# SzineszFeny_2mm_V12.net
KiCad netlist of a schematic drawn in EAGLE
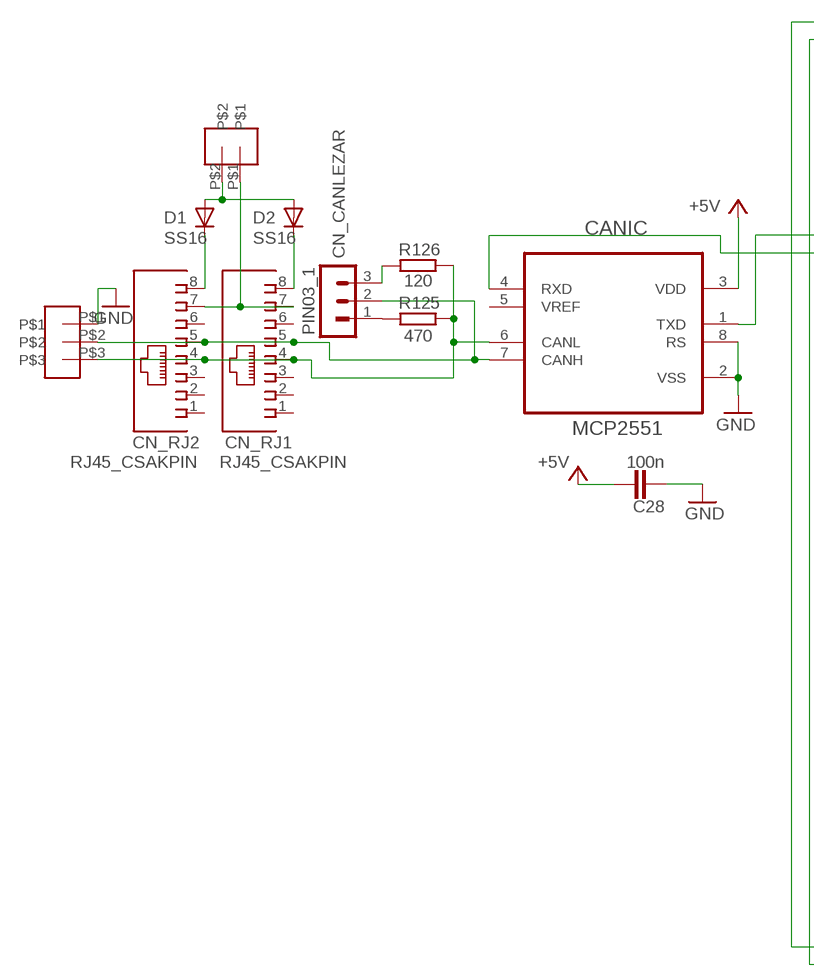
[diagram p0: schematic, sheet 1, part 1 of 2]
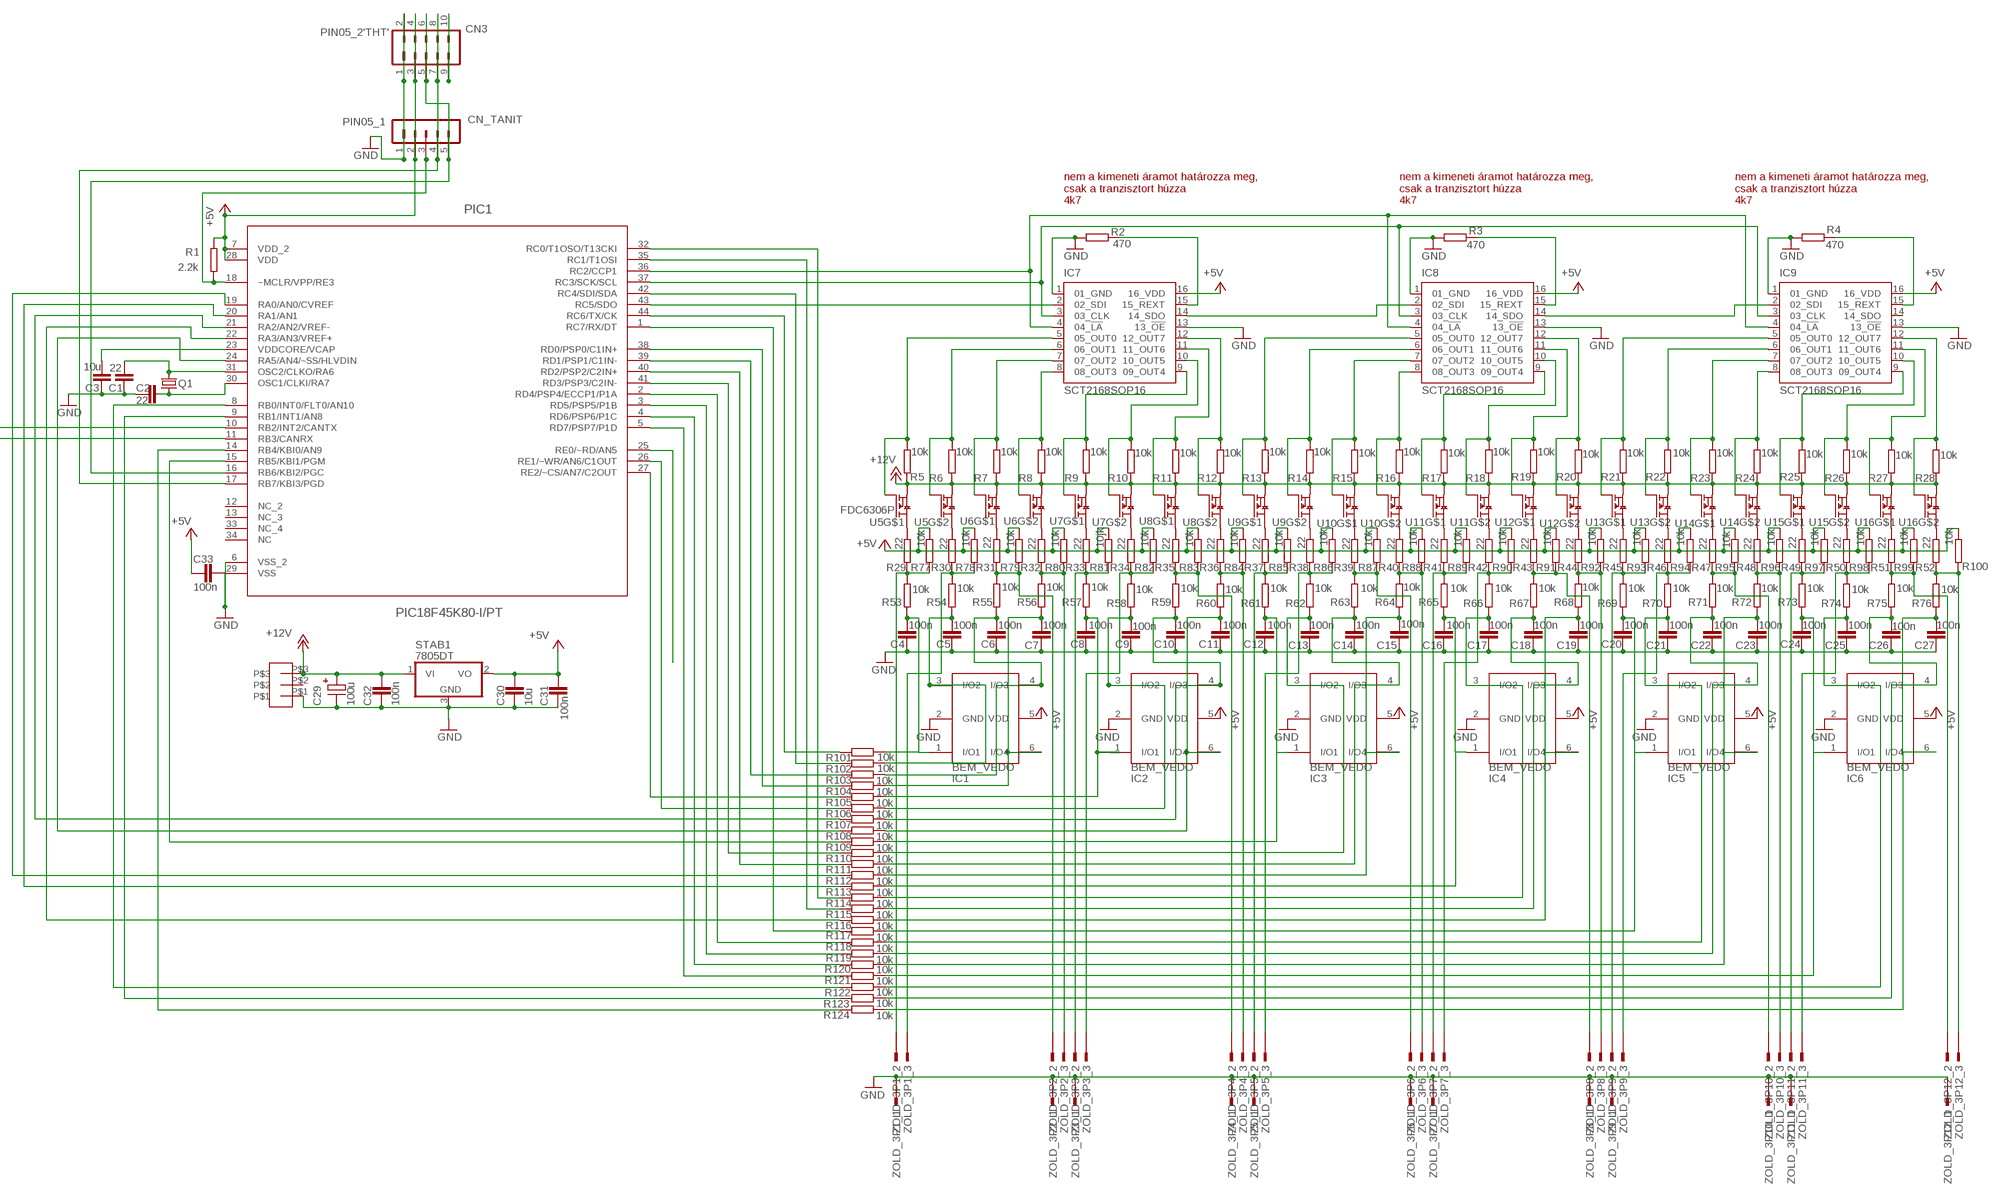
[diagram p1: schematic, sheet 1, part 2 of 2]

(export (version "E")
  (design (tool "Eeschema 10.0.6"))
  (components
    (comp (ref "C1")
      (value "22")
      (footprint "eagle-import:R0805")
      (libsource (lib "eagle-import") (part "C0805"))
    )
    (comp (ref "C2")
      (value "22")
      (footprint "eagle-import:R0805")
      (libsource (lib "eagle-import") (part "C0805"))
    )
    (comp (ref "C3")
      (value "10u")
      (footprint "eagle-import:R0805")
      (libsource (lib "eagle-import") (part "C0805"))
    )
    (comp (ref "C4")
      (value "100n")
      (footprint "eagle-import:R0805")
      (libsource (lib "eagle-import") (part "C0805"))
    )
    (comp (ref "C5")
      (value "100n")
      (footprint "eagle-import:R0805")
      (libsource (lib "eagle-import") (part "C0805"))
    )
    (comp (ref "C6")
      (value "100n")
      (footprint "eagle-import:R0805")
      (libsource (lib "eagle-import") (part "C0805"))
    )
    (comp (ref "C7")
      (value "100n")
      (footprint "eagle-import:R0805")
      (libsource (lib "eagle-import") (part "C0805"))
    )
    (comp (ref "C8")
      (value "100n")
      (footprint "eagle-import:R0805")
      (libsource (lib "eagle-import") (part "C0805"))
    )
    (comp (ref "C9")
      (value "100n")
      (footprint "eagle-import:R0805")
      (libsource (lib "eagle-import") (part "C0805"))
    )
    (comp (ref "C10")
      (value "100n")
      (footprint "eagle-import:R0805")
      (libsource (lib "eagle-import") (part "C0805"))
    )
    (comp (ref "C11")
      (value "100n")
      (footprint "eagle-import:R0805")
      (libsource (lib "eagle-import") (part "C0805"))
    )
    (comp (ref "C12")
      (value "100n")
      (footprint "eagle-import:R0805")
      (libsource (lib "eagle-import") (part "C0805"))
    )
    (comp (ref "C13")
      (value "100n")
      (footprint "eagle-import:R0805")
      (libsource (lib "eagle-import") (part "C0805"))
    )
    (comp (ref "C14")
      (value "100n")
      (footprint "eagle-import:R0805")
      (libsource (lib "eagle-import") (part "C0805"))
    )
    (comp (ref "C15")
      (value "100n")
      (footprint "eagle-import:R0805")
      (libsource (lib "eagle-import") (part "C0805"))
    )
    (comp (ref "C16")
      (value "100n")
      (footprint "eagle-import:R0805")
      (libsource (lib "eagle-import") (part "C0805"))
    )
    (comp (ref "C17")
      (value "100n")
      (footprint "eagle-import:R0805")
      (libsource (lib "eagle-import") (part "C0805"))
    )
    (comp (ref "C18")
      (value "100n")
      (footprint "eagle-import:R0805")
      (libsource (lib "eagle-import") (part "C0805"))
    )
    (comp (ref "C19")
      (value "100n")
      (footprint "eagle-import:R0805")
      (libsource (lib "eagle-import") (part "C0805"))
    )
    (comp (ref "C20")
      (value "100n")
      (footprint "eagle-import:R0805")
      (libsource (lib "eagle-import") (part "C0805"))
    )
    (comp (ref "C21")
      (value "100n")
      (footprint "eagle-import:R0805")
      (libsource (lib "eagle-import") (part "C0805"))
    )
    (comp (ref "C22")
      (value "100n")
      (footprint "eagle-import:R0805")
      (libsource (lib "eagle-import") (part "C0805"))
    )
    (comp (ref "C23")
      (value "100n")
      (footprint "eagle-import:R0805")
      (libsource (lib "eagle-import") (part "C0805"))
    )
    (comp (ref "C24")
      (value "100n")
      (footprint "eagle-import:R0805")
      (libsource (lib "eagle-import") (part "C0805"))
    )
    (comp (ref "C25")
      (value "100n")
      (footprint "eagle-import:R0805")
      (libsource (lib "eagle-import") (part "C0805"))
    )
    (comp (ref "C26")
      (value "100n")
      (footprint "eagle-import:R0805")
      (libsource (lib "eagle-import") (part "C0805"))
    )
    (comp (ref "C27")
      (value "100n")
      (footprint "eagle-import:R0805")
      (libsource (lib "eagle-import") (part "C0805"))
    )
    (comp (ref "C28")
      (value "100n")
      (footprint "eagle-import:R0805")
      (libsource (lib "eagle-import") (part "C0805"))
    )
    (comp (ref "C29")
      (value "100u")
      (footprint "eagle-import:C_EL1RASZT07")
      (libsource (lib "eagle-import") (part "C_EL1R07"))
    )
    (comp (ref "C30")
      (value "10u")
      (footprint "eagle-import:R0805")
      (libsource (lib "eagle-import") (part "C0805"))
    )
    (comp (ref "C31")
      (value "100n")
      (footprint "eagle-import:R0805")
      (libsource (lib "eagle-import") (part "C0805"))
    )
    (comp (ref "C32")
      (value "100n")
      (footprint "eagle-import:R0805")
      (libsource (lib "eagle-import") (part "C0805"))
    )
    (comp (ref "C33")
      (value "100n")
      (footprint "eagle-import:R0805")
      (libsource (lib "eagle-import") (part "C0805"))
    )
    (comp (ref "CANIC")
      (value "MCP2551")
      (footprint "eagle-import:DIP254P762X432-8")
      (fields (field (name "MPN") "MCP2551-I/P"))
      (libsource (lib "eagle-import") (part "MCP2551-I/P"))
    )
    (comp (ref "CN3")
      (value "PIN05_2'THT'")
      (footprint "eagle-import:PIN05_2")
      (libsource (lib "eagle-import") (part "PIN05_2'THT'"))
    )
    (comp (ref "CN_CANLEZAR")
      (value "PIN03_1")
      (footprint "eagle-import:PIN03_1")
      (libsource (lib "eagle-import") (part "PIN03_1"))
    )
    (comp (ref "CN_RJ1")
      (value "RJ45_CSAKPIN")
      (footprint "eagle-import:RJ45_CSAKPIN")
      (libsource (lib "eagle-import") (part "RJ45_CSAKPIN"))
    )
    (comp (ref "CN_RJ2")
      (value "RJ45_CSAKPIN")
      (footprint "eagle-import:RJ45_CSAKPIN")
      (libsource (lib "eagle-import") (part "RJ45_CSAKPIN"))
    )
    (comp (ref "CN_TANIT")
      (value "PIN05_1")
      (footprint "eagle-import:PIN05_1")
      (libsource (lib "eagle-import") (part "PIN05_1"))
    )
    (comp (ref "D1")
      (value "SS16")
      (footprint "eagle-import:DO214AC")
      (fields (field (name "D1") "SS16"))
      (libsource (lib "eagle-import") (part "DDO214AC"))
    )
    (comp (ref "D2")
      (value "SS16")
      (footprint "eagle-import:DO214AC")
      (fields (field (name "D2") "SS16"))
      (libsource (lib "eagle-import") (part "DDO214AC"))
    )
    (comp (ref "IC1")
      (value "BEM_VEDO")
      (footprint "eagle-import:TSOP-6")
      (libsource (lib "eagle-import") (part "BEM_VEDO"))
    )
    (comp (ref "IC2")
      (value "BEM_VEDO")
      (footprint "eagle-import:TSOP-6")
      (libsource (lib "eagle-import") (part "BEM_VEDO"))
    )
    (comp (ref "IC3")
      (value "BEM_VEDO")
      (footprint "eagle-import:TSOP-6")
      (libsource (lib "eagle-import") (part "BEM_VEDO"))
    )
    (comp (ref "IC4")
      (value "BEM_VEDO")
      (footprint "eagle-import:TSOP-6")
      (libsource (lib "eagle-import") (part "BEM_VEDO"))
    )
    (comp (ref "IC5")
      (value "BEM_VEDO")
      (footprint "eagle-import:TSOP-6")
      (libsource (lib "eagle-import") (part "BEM_VEDO"))
    )
    (comp (ref "IC6")
      (value "BEM_VEDO")
      (footprint "eagle-import:TSOP-6")
      (libsource (lib "eagle-import") (part "BEM_VEDO"))
    )
    (comp (ref "IC7")
      (value "SCT2168SOP16")
      (footprint "eagle-import:SO16")
      (libsource (lib "eagle-import") (part "SCT2168SOP16"))
    )
    (comp (ref "IC8")
      (value "SCT2168SOP16")
      (footprint "eagle-import:SO16")
      (libsource (lib "eagle-import") (part "SCT2168SOP16"))
    )
    (comp (ref "IC9")
      (value "SCT2168SOP16")
      (footprint "eagle-import:SO16")
      (libsource (lib "eagle-import") (part "SCT2168SOP16"))
    )
    (comp (ref "PIC1")
      (value "PIC18F45K80-I/PT")
      (footprint "eagle-import:QFP80P1200X1200X120-44N")
      (fields (field (name "MPN") "PIC18F4580-I/PT"))
      (libsource (lib "eagle-import") (part "PIC18F45K80-I/PT"))
    )
    (comp (ref "Q1")
      (value "XTAL_2QS")
      (footprint "eagle-import:XTAL_QS")
      (libsource (lib "eagle-import") (part "XTAL_2QS"))
    )
    (comp (ref "R1")
      (value "2.2k")
      (footprint "eagle-import:R0805@1")
      (libsource (lib "eagle-import") (part "R_EU0805"))
    )
    (comp (ref "R2")
      (value "470")
      (footprint "eagle-import:R0805@1")
      (libsource (lib "eagle-import") (part "R_EU0805"))
    )
    (comp (ref "R3")
      (value "470")
      (footprint "eagle-import:R0805@1")
      (libsource (lib "eagle-import") (part "R_EU0805"))
    )
    (comp (ref "R4")
      (value "470")
      (footprint "eagle-import:R0805@1")
      (libsource (lib "eagle-import") (part "R_EU0805"))
    )
    (comp (ref "R5")
      (value "10k")
      (footprint "eagle-import:R0805@1")
      (libsource (lib "eagle-import") (part "R_EU0805"))
    )
    (comp (ref "R6")
      (value "10k")
      (footprint "eagle-import:R0805@1")
      (libsource (lib "eagle-import") (part "R_EU0805"))
    )
    (comp (ref "R7")
      (value "10k")
      (footprint "eagle-import:R0805@1")
      (libsource (lib "eagle-import") (part "R_EU0805"))
    )
    (comp (ref "R8")
      (value "10k")
      (footprint "eagle-import:R0805@1")
      (libsource (lib "eagle-import") (part "R_EU0805"))
    )
    (comp (ref "R9")
      (value "10k")
      (footprint "eagle-import:R0805@1")
      (libsource (lib "eagle-import") (part "R_EU0805"))
    )
    (comp (ref "R10")
      (value "10k")
      (footprint "eagle-import:R0805@1")
      (libsource (lib "eagle-import") (part "R_EU0805"))
    )
    (comp (ref "R11")
      (value "10k")
      (footprint "eagle-import:R0805@1")
      (libsource (lib "eagle-import") (part "R_EU0805"))
    )
    (comp (ref "R12")
      (value "10k")
      (footprint "eagle-import:R0805@1")
      (libsource (lib "eagle-import") (part "R_EU0805"))
    )
    (comp (ref "R13")
      (value "10k")
      (footprint "eagle-import:R0805@1")
      (libsource (lib "eagle-import") (part "R_EU0805"))
    )
    (comp (ref "R14")
      (value "10k")
      (footprint "eagle-import:R0805@1")
      (libsource (lib "eagle-import") (part "R_EU0805"))
    )
    (comp (ref "R15")
      (value "10k")
      (footprint "eagle-import:R0805@1")
      (libsource (lib "eagle-import") (part "R_EU0805"))
    )
    (comp (ref "R16")
      (value "10k")
      (footprint "eagle-import:R0805@1")
      (libsource (lib "eagle-import") (part "R_EU0805"))
    )
    (comp (ref "R17")
      (value "10k")
      (footprint "eagle-import:R0805@1")
      (libsource (lib "eagle-import") (part "R_EU0805"))
    )
    (comp (ref "R18")
      (value "10k")
      (footprint "eagle-import:R0805@1")
      (libsource (lib "eagle-import") (part "R_EU0805"))
    )
    (comp (ref "R19")
      (value "10k")
      (footprint "eagle-import:R0805@1")
      (libsource (lib "eagle-import") (part "R_EU0805"))
    )
    (comp (ref "R20")
      (value "10k")
      (footprint "eagle-import:R0805@1")
      (libsource (lib "eagle-import") (part "R_EU0805"))
    )
    (comp (ref "R21")
      (value "10k")
      (footprint "eagle-import:R0805@1")
      (libsource (lib "eagle-import") (part "R_EU0805"))
    )
    (comp (ref "R22")
      (value "10k")
      (footprint "eagle-import:R0805@1")
      (libsource (lib "eagle-import") (part "R_EU0805"))
    )
    (comp (ref "R23")
      (value "10k")
      (footprint "eagle-import:R0805@1")
      (libsource (lib "eagle-import") (part "R_EU0805"))
    )
    (comp (ref "R24")
      (value "10k")
      (footprint "eagle-import:R0805@1")
      (libsource (lib "eagle-import") (part "R_EU0805"))
    )
    (comp (ref "R25")
      (value "10k")
      (footprint "eagle-import:R0805@1")
      (libsource (lib "eagle-import") (part "R_EU0805"))
    )
    (comp (ref "R26")
      (value "10k")
      (footprint "eagle-import:R0805@1")
      (libsource (lib "eagle-import") (part "R_EU0805"))
    )
    (comp (ref "R27")
      (value "10k")
      (footprint "eagle-import:R0805@1")
      (libsource (lib "eagle-import") (part "R_EU0805"))
    )
    (comp (ref "R28")
      (value "10k")
      (footprint "eagle-import:R0805@1")
      (libsource (lib "eagle-import") (part "R_EU0805"))
    )
    (comp (ref "R29")
      (value "22")
      (footprint "eagle-import:R0805@1")
      (libsource (lib "eagle-import") (part "R_EU0805"))
    )
    (comp (ref "R30")
      (value "22")
      (footprint "eagle-import:R0805@1")
      (libsource (lib "eagle-import") (part "R_EU0805"))
    )
    (comp (ref "R31")
      (value "22")
      (footprint "eagle-import:R0805@1")
      (libsource (lib "eagle-import") (part "R_EU0805"))
    )
    (comp (ref "R32")
      (value "22")
      (footprint "eagle-import:R0805@1")
      (libsource (lib "eagle-import") (part "R_EU0805"))
    )
    (comp (ref "R33")
      (value "22")
      (footprint "eagle-import:R0805@1")
      (libsource (lib "eagle-import") (part "R_EU0805"))
    )
    (comp (ref "R34")
      (value "22")
      (footprint "eagle-import:R0805@1")
      (libsource (lib "eagle-import") (part "R_EU0805"))
    )
    (comp (ref "R35")
      (value "22")
      (footprint "eagle-import:R0805@1")
      (libsource (lib "eagle-import") (part "R_EU0805"))
    )
    (comp (ref "R36")
      (value "22")
      (footprint "eagle-import:R0805@1")
      (libsource (lib "eagle-import") (part "R_EU0805"))
    )
    (comp (ref "R37")
      (value "22")
      (footprint "eagle-import:R0805@1")
      (libsource (lib "eagle-import") (part "R_EU0805"))
    )
    (comp (ref "R38")
      (value "22")
      (footprint "eagle-import:R0805@1")
      (libsource (lib "eagle-import") (part "R_EU0805"))
    )
    (comp (ref "R39")
      (value "22")
      (footprint "eagle-import:R0805@1")
      (libsource (lib "eagle-import") (part "R_EU0805"))
    )
    (comp (ref "R40")
      (value "22")
      (footprint "eagle-import:R0805@1")
      (libsource (lib "eagle-import") (part "R_EU0805"))
    )
    (comp (ref "R41")
      (value "22")
      (footprint "eagle-import:R0805@1")
      (libsource (lib "eagle-import") (part "R_EU0805"))
    )
    (comp (ref "R42")
      (value "22")
      (footprint "eagle-import:R0805@1")
      (libsource (lib "eagle-import") (part "R_EU0805"))
    )
    (comp (ref "R43")
      (value "22")
      (footprint "eagle-import:R0805@1")
      (libsource (lib "eagle-import") (part "R_EU0805"))
    )
    (comp (ref "R44")
      (value "22")
      (footprint "eagle-import:R0805@1")
      (libsource (lib "eagle-import") (part "R_EU0805"))
    )
    (comp (ref "R45")
      (value "22")
      (footprint "eagle-import:R0805@1")
      (libsource (lib "eagle-import") (part "R_EU0805"))
    )
    (comp (ref "R46")
      (value "22")
      (footprint "eagle-import:R0805@1")
      (libsource (lib "eagle-import") (part "R_EU0805"))
    )
    (comp (ref "R47")
      (value "22")
      (footprint "eagle-import:R0805@1")
      (libsource (lib "eagle-import") (part "R_EU0805"))
    )
    (comp (ref "R48")
      (value "22")
      (footprint "eagle-import:R0805@1")
      (libsource (lib "eagle-import") (part "R_EU0805"))
    )
    (comp (ref "R49")
      (value "22")
      (footprint "eagle-import:R0805@1")
      (libsource (lib "eagle-import") (part "R_EU0805"))
    )
    (comp (ref "R50")
      (value "22")
      (footprint "eagle-import:R0805@1")
      (libsource (lib "eagle-import") (part "R_EU0805"))
    )
    (comp (ref "R51")
      (value "22")
      (footprint "eagle-import:R0805@1")
      (libsource (lib "eagle-import") (part "R_EU0805"))
    )
    (comp (ref "R52")
      (value "22")
      (footprint "eagle-import:R0805@1")
      (libsource (lib "eagle-import") (part "R_EU0805"))
    )
    (comp (ref "R53")
      (value "10k")
      (footprint "eagle-import:R0805@1")
      (libsource (lib "eagle-import") (part "R_EU0805"))
    )
    (comp (ref "R54")
      (value "10k")
      (footprint "eagle-import:R0805@1")
      (libsource (lib "eagle-import") (part "R_EU0805"))
    )
    (comp (ref "R55")
      (value "10k")
      (footprint "eagle-import:R0805@1")
      (libsource (lib "eagle-import") (part "R_EU0805"))
    )
    (comp (ref "R56")
      (value "10k")
      (footprint "eagle-import:R0805@1")
      (libsource (lib "eagle-import") (part "R_EU0805"))
    )
    (comp (ref "R57")
      (value "10k")
      (footprint "eagle-import:R0805@1")
      (libsource (lib "eagle-import") (part "R_EU0805"))
    )
    (comp (ref "R58")
      (value "10k")
      (footprint "eagle-import:R0805@1")
      (libsource (lib "eagle-import") (part "R_EU0805"))
    )
    (comp (ref "R59")
      (value "10k")
      (footprint "eagle-import:R0805@1")
      (libsource (lib "eagle-import") (part "R_EU0805"))
    )
    (comp (ref "R60")
      (value "10k")
      (footprint "eagle-import:R0805@1")
      (libsource (lib "eagle-import") (part "R_EU0805"))
    )
    (comp (ref "R61")
      (value "10k")
      (footprint "eagle-import:R0805@1")
      (libsource (lib "eagle-import") (part "R_EU0805"))
    )
    (comp (ref "R62")
      (value "10k")
      (footprint "eagle-import:R0805@1")
      (libsource (lib "eagle-import") (part "R_EU0805"))
    )
    (comp (ref "R63")
      (value "10k")
      (footprint "eagle-import:R0805@1")
      (libsource (lib "eagle-import") (part "R_EU0805"))
    )
    (comp (ref "R64")
      (value "10k")
      (footprint "eagle-import:R0805@1")
      (libsource (lib "eagle-import") (part "R_EU0805"))
    )
    (comp (ref "R65")
      (value "10k")
      (footprint "eagle-import:R0805@1")
      (libsource (lib "eagle-import") (part "R_EU0805"))
    )
    (comp (ref "R66")
      (value "10k")
      (footprint "eagle-import:R0805@1")
      (libsource (lib "eagle-import") (part "R_EU0805"))
    )
    (comp (ref "R67")
      (value "10k")
      (footprint "eagle-import:R0805@1")
      (libsource (lib "eagle-import") (part "R_EU0805"))
    )
    (comp (ref "R68")
      (value "10k")
      (footprint "eagle-import:R0805@1")
      (libsource (lib "eagle-import") (part "R_EU0805"))
    )
    (comp (ref "R69")
      (value "10k")
      (footprint "eagle-import:R0805@1")
      (libsource (lib "eagle-import") (part "R_EU0805"))
    )
    (comp (ref "R70")
      (value "10k")
      (footprint "eagle-import:R0805@1")
      (libsource (lib "eagle-import") (part "R_EU0805"))
    )
    (comp (ref "R71")
      (value "10k")
      (footprint "eagle-import:R0805@1")
      (libsource (lib "eagle-import") (part "R_EU0805"))
    )
    (comp (ref "R72")
      (value "10k")
      (footprint "eagle-import:R0805@1")
      (libsource (lib "eagle-import") (part "R_EU0805"))
    )
    (comp (ref "R73")
      (value "10k")
      (footprint "eagle-import:R0805@1")
      (libsource (lib "eagle-import") (part "R_EU0805"))
    )
    (comp (ref "R74")
      (value "10k")
      (footprint "eagle-import:R0805@1")
      (libsource (lib "eagle-import") (part "R_EU0805"))
    )
    (comp (ref "R75")
      (value "10k")
      (footprint "eagle-import:R0805@1")
      (libsource (lib "eagle-import") (part "R_EU0805"))
    )
    (comp (ref "R76")
      (value "10k")
      (footprint "eagle-import:R0805@1")
      (libsource (lib "eagle-import") (part "R_EU0805"))
    )
    (comp (ref "R77")
      (value "10k")
      (footprint "eagle-import:R0805@1")
      (libsource (lib "eagle-import") (part "R_EU0805"))
    )
    (comp (ref "R78")
      (value "10k")
      (footprint "eagle-import:R0805@1")
      (libsource (lib "eagle-import") (part "R_EU0805"))
    )
    (comp (ref "R79")
      (value "10k")
      (footprint "eagle-import:R0805@1")
      (libsource (lib "eagle-import") (part "R_EU0805"))
    )
    (comp (ref "R80")
      (value "10k")
      (footprint "eagle-import:R0805@1")
      (libsource (lib "eagle-import") (part "R_EU0805"))
    )
    (comp (ref "R81")
      (value "10jk")
      (footprint "eagle-import:R0805@1")
      (libsource (lib "eagle-import") (part "R_EU0805"))
    )
    (comp (ref "R82")
      (value "10k")
      (footprint "eagle-import:R0805@1")
      (libsource (lib "eagle-import") (part "R_EU0805"))
    )
    (comp (ref "R83")
      (value "10k")
      (footprint "eagle-import:R0805@1")
      (libsource (lib "eagle-import") (part "R_EU0805"))
    )
    (comp (ref "R84")
      (value "10k")
      (footprint "eagle-import:R0805@1")
      (libsource (lib "eagle-import") (part "R_EU0805"))
    )
    (comp (ref "R85")
      (value "10k")
      (footprint "eagle-import:R0805@1")
      (libsource (lib "eagle-import") (part "R_EU0805"))
    )
    (comp (ref "R86")
      (value "10k")
      (footprint "eagle-import:R0805@1")
      (libsource (lib "eagle-import") (part "R_EU0805"))
    )
    (comp (ref "R87")
      (value "10k")
      (footprint "eagle-import:R0805@1")
      (libsource (lib "eagle-import") (part "R_EU0805"))
    )
    (comp (ref "R88")
      (value "10k")
      (footprint "eagle-import:R0805@1")
      (libsource (lib "eagle-import") (part "R_EU0805"))
    )
    (comp (ref "R89")
      (value "10k")
      (footprint "eagle-import:R0805@1")
      (libsource (lib "eagle-import") (part "R_EU0805"))
    )
    (comp (ref "R90")
      (value "10k")
      (footprint "eagle-import:R0805@1")
      (libsource (lib "eagle-import") (part "R_EU0805"))
    )
    (comp (ref "R91")
      (value "10k")
      (footprint "eagle-import:R0805@1")
      (libsource (lib "eagle-import") (part "R_EU0805"))
    )
    (comp (ref "R92")
      (value "10k")
      (footprint "eagle-import:R0805@1")
      (libsource (lib "eagle-import") (part "R_EU0805"))
    )
    (comp (ref "R93")
      (value "10k")
      (footprint "eagle-import:R0805@1")
      (libsource (lib "eagle-import") (part "R_EU0805"))
    )
    (comp (ref "R94")
      (value "10k")
      (footprint "eagle-import:R0805@1")
      (libsource (lib "eagle-import") (part "R_EU0805"))
    )
    (comp (ref "R95")
      (value "10k")
      (footprint "eagle-import:R0805@1")
      (libsource (lib "eagle-import") (part "R_EU0805"))
    )
    (comp (ref "R96")
      (value "10k")
      (footprint "eagle-import:R0805@1")
      (libsource (lib "eagle-import") (part "R_EU0805"))
    )
    (comp (ref "R97")
      (value "10k")
      (footprint "eagle-import:R0805@1")
      (libsource (lib "eagle-import") (part "R_EU0805"))
    )
    (comp (ref "R98")
      (value "10k")
      (footprint "eagle-import:R0805@1")
      (libsource (lib "eagle-import") (part "R_EU0805"))
    )
    (comp (ref "R99")
      (value "10k")
      (footprint "eagle-import:R0805@1")
      (libsource (lib "eagle-import") (part "R_EU0805"))
    )
    (comp (ref "R100")
      (value "10k")
      (footprint "eagle-import:R0805@1")
      (libsource (lib "eagle-import") (part "R_EU0805"))
    )
    (comp (ref "R101")
      (value "10k")
      (footprint "eagle-import:R0805@1")
      (libsource (lib "eagle-import") (part "R_EU0805"))
    )
    (comp (ref "R102")
      (value "10k")
      (footprint "eagle-import:R0805@1")
      (libsource (lib "eagle-import") (part "R_EU0805"))
    )
    (comp (ref "R103")
      (value "10k")
      (footprint "eagle-import:R0805@1")
      (libsource (lib "eagle-import") (part "R_EU0805"))
    )
    (comp (ref "R104")
      (value "10k")
      (footprint "eagle-import:R0805@1")
      (libsource (lib "eagle-import") (part "R_EU0805"))
    )
    (comp (ref "R105")
      (value "10k")
      (footprint "eagle-import:R0805@1")
      (libsource (lib "eagle-import") (part "R_EU0805"))
    )
    (comp (ref "R106")
      (value "10k")
      (footprint "eagle-import:R0805@1")
      (libsource (lib "eagle-import") (part "R_EU0805"))
    )
    (comp (ref "R107")
      (value "10k")
      (footprint "eagle-import:R0805@1")
      (libsource (lib "eagle-import") (part "R_EU0805"))
    )
    (comp (ref "R108")
      (value "10k")
      (footprint "eagle-import:R0805@1")
      (libsource (lib "eagle-import") (part "R_EU0805"))
    )
    (comp (ref "R109")
      (value "10k")
      (footprint "eagle-import:R0805@1")
      (libsource (lib "eagle-import") (part "R_EU0805"))
    )
    (comp (ref "R110")
      (value "10k")
      (footprint "eagle-import:R0805@1")
      (libsource (lib "eagle-import") (part "R_EU0805"))
    )
    (comp (ref "R111")
      (value "10k")
      (footprint "eagle-import:R0805@1")
      (libsource (lib "eagle-import") (part "R_EU0805"))
    )
    (comp (ref "R112")
      (value "10k")
      (footprint "eagle-import:R0805@1")
      (libsource (lib "eagle-import") (part "R_EU0805"))
    )
    (comp (ref "R113")
      (value "10k")
      (footprint "eagle-import:R0805@1")
      (libsource (lib "eagle-import") (part "R_EU0805"))
    )
    (comp (ref "R114")
      (value "10k")
      (footprint "eagle-import:R0805@1")
      (libsource (lib "eagle-import") (part "R_EU0805"))
    )
    (comp (ref "R115")
      (value "10k")
      (footprint "eagle-import:R0805@1")
      (libsource (lib "eagle-import") (part "R_EU0805"))
    )
    (comp (ref "R116")
      (value "10k")
      (footprint "eagle-import:R0805@1")
      (libsource (lib "eagle-import") (part "R_EU0805"))
    )
    (comp (ref "R117")
      (value "10k")
      (footprint "eagle-import:R0805@1")
      (libsource (lib "eagle-import") (part "R_EU0805"))
    )
    (comp (ref "R118")
      (value "10k")
      (footprint "eagle-import:R0805@1")
      (libsource (lib "eagle-import") (part "R_EU0805"))
    )
    (comp (ref "R119")
      (value "10k")
      (footprint "eagle-import:R0805@1")
      (libsource (lib "eagle-import") (part "R_EU0805"))
    )
    (comp (ref "R120")
      (value "10k")
      (footprint "eagle-import:R0805@1")
      (libsource (lib "eagle-import") (part "R_EU0805"))
    )
    (comp (ref "R121")
      (value "10k")
      (footprint "eagle-import:R0805@1")
      (libsource (lib "eagle-import") (part "R_EU0805"))
    )
    (comp (ref "R122")
      (value "10k")
      (footprint "eagle-import:R0805@1")
      (libsource (lib "eagle-import") (part "R_EU0805"))
    )
    (comp (ref "R123")
      (value "10k")
      (footprint "eagle-import:R0805@1")
      (libsource (lib "eagle-import") (part "R_EU0805"))
    )
    (comp (ref "R124")
      (value "10k")
      (footprint "eagle-import:R0805@1")
      (libsource (lib "eagle-import") (part "R_EU0805"))
    )
    (comp (ref "R125")
      (value "470")
      (footprint "eagle-import:R0805@1")
      (libsource (lib "eagle-import") (part "R_EU0805"))
    )
    (comp (ref "R126")
      (value "120")
      (footprint "eagle-import:R0805@1")
      (libsource (lib "eagle-import") (part "R_EU0805"))
    )
    (comp (ref "STAB1")
      (value "7805DT")
      (footprint "eagle-import:TO252")
      (libsource (lib "eagle-import") (part "78DT05"))
    )
    (comp (ref "U$1")
      (value "FEHER_TUS_3")
      (footprint "eagle-import:FEHER_TUS_3")
      (libsource (lib "eagle-import") (part "FEHER_TUS_3"))
    )
    (comp (ref "U$20")
      (value "FEHER_TUS_3")
      (footprint "eagle-import:FEHER_TUS_3")
      (libsource (lib "eagle-import") (part "FEHER_TUS_3"))
    )
    (comp (ref "U$21")
      (value "FEHER_TUS_2ALLO")
      (footprint "eagle-import:FEHER_TUS_2")
      (libsource (lib "eagle-import") (part "FEHER_TUS_2ALLO"))
    )
    (comp (ref "U5")
      (value "FDC6306P")
      (footprint "eagle-import:SOT26")
      (libsource (lib "eagle-import") (part "AP2625GY-HF-3SOT26"))
    )
    (comp (ref "U6")
      (value "AP2625GY-HF-3SOT26")
      (footprint "eagle-import:SOT26")
      (libsource (lib "eagle-import") (part "AP2625GY-HF-3SOT26"))
    )
    (comp (ref "U7")
      (value "AP2625GY-HF-3SOT26")
      (footprint "eagle-import:SOT26")
      (libsource (lib "eagle-import") (part "AP2625GY-HF-3SOT26"))
    )
    (comp (ref "U8")
      (value "AP2625GY-HF-3SOT26")
      (footprint "eagle-import:SOT26")
      (libsource (lib "eagle-import") (part "AP2625GY-HF-3SOT26"))
    )
    (comp (ref "U9")
      (value "AP2625GY-HF-3SOT26")
      (footprint "eagle-import:SOT26")
      (libsource (lib "eagle-import") (part "AP2625GY-HF-3SOT26"))
    )
    (comp (ref "U10")
      (value "AP2625GY-HF-3SOT26")
      (footprint "eagle-import:SOT26")
      (libsource (lib "eagle-import") (part "AP2625GY-HF-3SOT26"))
    )
    (comp (ref "U11")
      (value "AP2625GY-HF-3SOT26")
      (footprint "eagle-import:SOT26")
      (libsource (lib "eagle-import") (part "AP2625GY-HF-3SOT26"))
    )
    (comp (ref "U12")
      (value "AP2625GY-HF-3SOT26")
      (footprint "eagle-import:SOT26")
      (libsource (lib "eagle-import") (part "AP2625GY-HF-3SOT26"))
    )
    (comp (ref "U13")
      (value "AP2625GY-HF-3SOT26")
      (footprint "eagle-import:SOT26")
      (libsource (lib "eagle-import") (part "AP2625GY-HF-3SOT26"))
    )
    (comp (ref "U14")
      (value "AP2625GY-HF-3SOT26")
      (footprint "eagle-import:SOT26")
      (libsource (lib "eagle-import") (part "AP2625GY-HF-3SOT26"))
    )
    (comp (ref "U15")
      (value "AP2625GY-HF-3SOT26")
      (footprint "eagle-import:SOT26")
      (libsource (lib "eagle-import") (part "AP2625GY-HF-3SOT26"))
    )
    (comp (ref "U16")
      (value "FDC6306P")
      (footprint "eagle-import:SOT26")
      (libsource (lib "eagle-import") (part "AP2625GY-HF-3SOT26"))
    )
    (comp (ref "ZOLD_3P1")
      (value "ZOLD_KICSI_3P")
      (footprint "eagle-import:ZOLD_KICSI_3P")
      (libsource (lib "eagle-import") (part "ZOLD_KICSI_3P"))
    )
    (comp (ref "ZOLD_3P2")
      (value "ZOLD_KICSI_3P")
      (footprint "eagle-import:ZOLD_KICSI_3P")
      (libsource (lib "eagle-import") (part "ZOLD_KICSI_3P"))
    )
    (comp (ref "ZOLD_3P3")
      (value "ZOLD_KICSI_3P")
      (footprint "eagle-import:ZOLD_KICSI_3P")
      (libsource (lib "eagle-import") (part "ZOLD_KICSI_3P"))
    )
    (comp (ref "ZOLD_3P4")
      (value "ZOLD_KICSI_3P")
      (footprint "eagle-import:ZOLD_KICSI_3P")
      (libsource (lib "eagle-import") (part "ZOLD_KICSI_3P"))
    )
    (comp (ref "ZOLD_3P5")
      (value "ZOLD_KICSI_3P")
      (footprint "eagle-import:ZOLD_KICSI_3P")
      (libsource (lib "eagle-import") (part "ZOLD_KICSI_3P"))
    )
    (comp (ref "ZOLD_3P6")
      (value "ZOLD_KICSI_3P")
      (footprint "eagle-import:ZOLD_KICSI_3P")
      (libsource (lib "eagle-import") (part "ZOLD_KICSI_3P"))
    )
    (comp (ref "ZOLD_3P7")
      (value "ZOLD_KICSI_3P")
      (footprint "eagle-import:ZOLD_KICSI_3P")
      (libsource (lib "eagle-import") (part "ZOLD_KICSI_3P"))
    )
    (comp (ref "ZOLD_3P8")
      (value "ZOLD_KICSI_3P")
      (footprint "eagle-import:ZOLD_KICSI_3P")
      (libsource (lib "eagle-import") (part "ZOLD_KICSI_3P"))
    )
    (comp (ref "ZOLD_3P9")
      (value "ZOLD_KICSI_3P")
      (footprint "eagle-import:ZOLD_KICSI_3P")
      (libsource (lib "eagle-import") (part "ZOLD_KICSI_3P"))
    )
    (comp (ref "ZOLD_3P10")
      (value "ZOLD_KICSI_3P")
      (footprint "eagle-import:ZOLD_KICSI_3P")
      (libsource (lib "eagle-import") (part "ZOLD_KICSI_3P"))
    )
    (comp (ref "ZOLD_3P11")
      (value "ZOLD_KICSI_3P")
      (footprint "eagle-import:ZOLD_KICSI_3P")
      (libsource (lib "eagle-import") (part "ZOLD_KICSI_3P"))
    )
    (comp (ref "ZOLD_3P12")
      (value "ZOLD_KICSI_3P")
      (footprint "eagle-import:ZOLD_KICSI_3P")
      (libsource (lib "eagle-import") (part "ZOLD_KICSI_3P"))
    )
  )
  (nets
    (net (code "1") (name "+5V") (class "Default")
      (node (ref "C28") (pin "1") (pinfunction "1_1") (pintype "passive"))
      (node (ref "C30") (pin "1") (pinfunction "1_1") (pintype "passive"))
      (node (ref "C31") (pin "1") (pinfunction "1_1") (pintype "passive"))
      (node (ref "C33") (pin "2") (pinfunction "2_2") (pintype "passive"))
      (node (ref "CANIC") (pin "3") (pinfunction "VDD_3") (pintype "power_in"))
      (node (ref "CN3") (pin "3") (pinfunction "3_3") (pintype "passive"))
      (node (ref "CN3") (pin "4") (pinfunction "4_4") (pintype "passive"))
      (node (ref "CN_TANIT") (pin "2") (pinfunction "2_2") (pintype "passive"))
      (node (ref "IC1") (pin "5") (pinfunction "VDD_5") (pintype "bidirectional"))
      (node (ref "IC2") (pin "5") (pinfunction "VDD_5") (pintype "bidirectional"))
      (node (ref "IC3") (pin "5") (pinfunction "VDD_5") (pintype "bidirectional"))
      (node (ref "IC4") (pin "5") (pinfunction "VDD_5") (pintype "bidirectional"))
      (node (ref "IC5") (pin "5") (pinfunction "VDD_5") (pintype "bidirectional"))
      (node (ref "IC6") (pin "5") (pinfunction "VDD_5") (pintype "bidirectional"))
      (node (ref "IC7") (pin "16") (pinfunction "16_VDD_16") (pintype "power_in"))
      (node (ref "IC8") (pin "16") (pinfunction "16_VDD_16") (pintype "power_in"))
      (node (ref "IC9") (pin "16") (pinfunction "16_VDD_16") (pintype "power_in"))
      (node (ref "PIC1") (pin "28") (pinfunction "VDD_28") (pintype "power_in"))
      (node (ref "PIC1") (pin "7") (pinfunction "VDD_2_7") (pintype "power_in"))
      (node (ref "R1") (pin "2") (pinfunction "E_2") (pintype "passive"))
      (node (ref "R100") (pin "1") (pinfunction "A_1") (pintype "passive"))
      (node (ref "R77") (pin "1") (pinfunction "A_1") (pintype "passive"))
      (node (ref "R78") (pin "1") (pinfunction "A_1") (pintype "passive"))
      (node (ref "R79") (pin "1") (pinfunction "A_1") (pintype "passive"))
      (node (ref "R80") (pin "1") (pinfunction "A_1") (pintype "passive"))
      (node (ref "R81") (pin "1") (pinfunction "A_1") (pintype "passive"))
      (node (ref "R82") (pin "1") (pinfunction "A_1") (pintype "passive"))
      (node (ref "R83") (pin "1") (pinfunction "A_1") (pintype "passive"))
      (node (ref "R84") (pin "1") (pinfunction "A_1") (pintype "passive"))
      (node (ref "R85") (pin "1") (pinfunction "A_1") (pintype "passive"))
      (node (ref "R86") (pin "1") (pinfunction "A_1") (pintype "passive"))
      (node (ref "R87") (pin "1") (pinfunction "A_1") (pintype "passive"))
      (node (ref "R88") (pin "1") (pinfunction "A_1") (pintype "passive"))
      (node (ref "R89") (pin "1") (pinfunction "A_1") (pintype "passive"))
      (node (ref "R90") (pin "1") (pinfunction "A_1") (pintype "passive"))
      (node (ref "R91") (pin "1") (pinfunction "A_1") (pintype "passive"))
      (node (ref "R92") (pin "1") (pinfunction "A_1") (pintype "passive"))
      (node (ref "R93") (pin "1") (pinfunction "A_1") (pintype "passive"))
      (node (ref "R94") (pin "1") (pinfunction "A_1") (pintype "passive"))
      (node (ref "R95") (pin "1") (pinfunction "A_1") (pintype "passive"))
      (node (ref "R96") (pin "1") (pinfunction "A_1") (pintype "passive"))
      (node (ref "R97") (pin "1") (pinfunction "A_1") (pintype "passive"))
      (node (ref "R98") (pin "1") (pinfunction "A_1") (pintype "passive"))
      (node (ref "R99") (pin "1") (pinfunction "A_1") (pintype "passive"))
      (node (ref "STAB1") (pin "2") (pinfunction "VO_2") (pintype "passive"))
    )
    (net (code "2") (name "+12V") (class "Default")
      (node (ref "C29") (pin "P+") (pinfunction "P+_P+") (pintype "passive"))
      (node (ref "C32") (pin "1") (pinfunction "1_1") (pintype "passive"))
      (node (ref "R10") (pin "1") (pinfunction "A_1") (pintype "passive"))
      (node (ref "R11") (pin "1") (pinfunction "A_1") (pintype "passive"))
      (node (ref "R12") (pin "1") (pinfunction "A_1") (pintype "passive"))
      (node (ref "R13") (pin "1") (pinfunction "A_1") (pintype "passive"))
      (node (ref "R14") (pin "1") (pinfunction "A_1") (pintype "passive"))
      (node (ref "R15") (pin "1") (pinfunction "A_1") (pintype "passive"))
      (node (ref "R16") (pin "1") (pinfunction "A_1") (pintype "passive"))
      (node (ref "R17") (pin "1") (pinfunction "A_1") (pintype "passive"))
      (node (ref "R18") (pin "1") (pinfunction "A_1") (pintype "passive"))
      (node (ref "R19") (pin "1") (pinfunction "A_1") (pintype "passive"))
      (node (ref "R20") (pin "1") (pinfunction "A_1") (pintype "passive"))
      (node (ref "R21") (pin "1") (pinfunction "A_1") (pintype "passive"))
      (node (ref "R22") (pin "1") (pinfunction "A_1") (pintype "passive"))
      (node (ref "R23") (pin "1") (pinfunction "A_1") (pintype "passive"))
      (node (ref "R24") (pin "1") (pinfunction "A_1") (pintype "passive"))
      (node (ref "R25") (pin "1") (pinfunction "A_1") (pintype "passive"))
      (node (ref "R26") (pin "1") (pinfunction "A_1") (pintype "passive"))
      (node (ref "R27") (pin "1") (pinfunction "A_1") (pintype "passive"))
      (node (ref "R28") (pin "1") (pinfunction "A_1") (pintype "passive"))
      (node (ref "R5") (pin "1") (pinfunction "A_1") (pintype "passive"))
      (node (ref "R6") (pin "1") (pinfunction "A_1") (pintype "passive"))
      (node (ref "R7") (pin "1") (pinfunction "A_1") (pintype "passive"))
      (node (ref "R8") (pin "1") (pinfunction "A_1") (pintype "passive"))
      (node (ref "R9") (pin "1") (pinfunction "A_1") (pintype "passive"))
      (node (ref "STAB1") (pin "1") (pinfunction "VI_1") (pintype "input"))
      (node (ref "U$20") (pin "P$3") (pinfunction "P$3_P$3") (pintype "bidirectional"))
      (node (ref "U10") (pin "P$2") (pinfunction "S_P$2") (pintype "passive"))
      (node (ref "U10") (pin "P$5") (pinfunction "S_P$5") (pintype "passive"))
      (node (ref "U11") (pin "P$2") (pinfunction "S_P$2") (pintype "passive"))
      (node (ref "U11") (pin "P$5") (pinfunction "S_P$5") (pintype "passive"))
      (node (ref "U12") (pin "P$2") (pinfunction "S_P$2") (pintype "passive"))
      (node (ref "U12") (pin "P$5") (pinfunction "S_P$5") (pintype "passive"))
      (node (ref "U13") (pin "P$2") (pinfunction "S_P$2") (pintype "passive"))
      (node (ref "U13") (pin "P$5") (pinfunction "S_P$5") (pintype "passive"))
      (node (ref "U14") (pin "P$2") (pinfunction "S_P$2") (pintype "passive"))
      (node (ref "U14") (pin "P$5") (pinfunction "S_P$5") (pintype "passive"))
      (node (ref "U15") (pin "P$2") (pinfunction "S_P$2") (pintype "passive"))
      (node (ref "U15") (pin "P$5") (pinfunction "S_P$5") (pintype "passive"))
      (node (ref "U16") (pin "P$2") (pinfunction "S_P$2") (pintype "passive"))
      (node (ref "U16") (pin "P$5") (pinfunction "S_P$5") (pintype "passive"))
      (node (ref "U5") (pin "P$2") (pinfunction "S_P$2") (pintype "passive"))
      (node (ref "U5") (pin "P$5") (pinfunction "S_P$5") (pintype "passive"))
      (node (ref "U6") (pin "P$2") (pinfunction "S_P$2") (pintype "passive"))
      (node (ref "U6") (pin "P$5") (pinfunction "S_P$5") (pintype "passive"))
      (node (ref "U7") (pin "P$2") (pinfunction "S_P$2") (pintype "passive"))
      (node (ref "U7") (pin "P$5") (pinfunction "S_P$5") (pintype "passive"))
      (node (ref "U8") (pin "P$2") (pinfunction "S_P$2") (pintype "passive"))
      (node (ref "U8") (pin "P$5") (pinfunction "S_P$5") (pintype "passive"))
      (node (ref "U9") (pin "P$2") (pinfunction "S_P$2") (pintype "passive"))
      (node (ref "U9") (pin "P$5") (pinfunction "S_P$5") (pintype "passive"))
    )
    (net (code "3") (name "GND") (class "Default")
      (node (ref "C1") (pin "2") (pinfunction "2_2") (pintype "passive"))
      (node (ref "C10") (pin "2") (pinfunction "2_2") (pintype "passive"))
      (node (ref "C11") (pin "2") (pinfunction "2_2") (pintype "passive"))
      (node (ref "C12") (pin "2") (pinfunction "2_2") (pintype "passive"))
      (node (ref "C13") (pin "2") (pinfunction "2_2") (pintype "passive"))
      (node (ref "C14") (pin "2") (pinfunction "2_2") (pintype "passive"))
      (node (ref "C15") (pin "2") (pinfunction "2_2") (pintype "passive"))
      (node (ref "C16") (pin "2") (pinfunction "2_2") (pintype "passive"))
      (node (ref "C17") (pin "2") (pinfunction "2_2") (pintype "passive"))
      (node (ref "C18") (pin "2") (pinfunction "2_2") (pintype "passive"))
      (node (ref "C19") (pin "2") (pinfunction "2_2") (pintype "passive"))
      (node (ref "C2") (pin "2") (pinfunction "2_2") (pintype "passive"))
      (node (ref "C20") (pin "2") (pinfunction "2_2") (pintype "passive"))
      (node (ref "C21") (pin "2") (pinfunction "2_2") (pintype "passive"))
      (node (ref "C22") (pin "2") (pinfunction "2_2") (pintype "passive"))
      (node (ref "C23") (pin "2") (pinfunction "2_2") (pintype "passive"))
      (node (ref "C24") (pin "2") (pinfunction "2_2") (pintype "passive"))
      (node (ref "C25") (pin "2") (pinfunction "2_2") (pintype "passive"))
      (node (ref "C26") (pin "2") (pinfunction "2_2") (pintype "passive"))
      (node (ref "C27") (pin "2") (pinfunction "2_2") (pintype "passive"))
      (node (ref "C28") (pin "2") (pinfunction "2_2") (pintype "passive"))
      (node (ref "C29") (pin "P-") (pinfunction "P-_P-") (pintype "passive"))
      (node (ref "C3") (pin "2") (pinfunction "2_2") (pintype "passive"))
      (node (ref "C30") (pin "2") (pinfunction "2_2") (pintype "passive"))
      (node (ref "C31") (pin "2") (pinfunction "2_2") (pintype "passive"))
      (node (ref "C32") (pin "2") (pinfunction "2_2") (pintype "passive"))
      (node (ref "C33") (pin "1") (pinfunction "1_1") (pintype "passive"))
      (node (ref "C4") (pin "2") (pinfunction "2_2") (pintype "passive"))
      (node (ref "C5") (pin "2") (pinfunction "2_2") (pintype "passive"))
      (node (ref "C6") (pin "2") (pinfunction "2_2") (pintype "passive"))
      (node (ref "C7") (pin "2") (pinfunction "2_2") (pintype "passive"))
      (node (ref "C8") (pin "2") (pinfunction "2_2") (pintype "passive"))
      (node (ref "C9") (pin "2") (pinfunction "2_2") (pintype "passive"))
      (node (ref "CANIC") (pin "2") (pinfunction "VSS_2") (pintype "power_in"))
      (node (ref "CANIC") (pin "8") (pinfunction "RS_8") (pintype "input"))
      (node (ref "CN3") (pin "1") (pinfunction "1_1") (pintype "passive"))
      (node (ref "CN3") (pin "2") (pinfunction "2_2") (pintype "passive"))
      (node (ref "CN_TANIT") (pin "1") (pinfunction "1_1") (pintype "passive"))
      (node (ref "IC1") (pin "2") (pinfunction "GND_2") (pintype "bidirectional"))
      (node (ref "IC2") (pin "2") (pinfunction "GND_2") (pintype "bidirectional"))
      (node (ref "IC3") (pin "2") (pinfunction "GND_2") (pintype "bidirectional"))
      (node (ref "IC4") (pin "2") (pinfunction "GND_2") (pintype "bidirectional"))
      (node (ref "IC5") (pin "2") (pinfunction "GND_2") (pintype "bidirectional"))
      (node (ref "IC6") (pin "2") (pinfunction "GND_2") (pintype "bidirectional"))
      (node (ref "IC7") (pin "1") (pinfunction "01_GND_1") (pintype "power_in"))
      (node (ref "IC7") (pin "13") (pinfunction "13_~{OE}_13") (pintype "input"))
      (node (ref "IC8") (pin "1") (pinfunction "01_GND_1") (pintype "power_in"))
      (node (ref "IC8") (pin "13") (pinfunction "13_~{OE}_13") (pintype "input"))
      (node (ref "IC9") (pin "1") (pinfunction "01_GND_1") (pintype "power_in"))
      (node (ref "IC9") (pin "13") (pinfunction "13_~{OE}_13") (pintype "input"))
      (node (ref "PIC1") (pin "29") (pinfunction "VSS_29") (pintype "power_in"))
      (node (ref "PIC1") (pin "6") (pinfunction "VSS_2_6") (pintype "power_in"))
      (node (ref "R2") (pin "1") (pinfunction "A_1") (pintype "passive"))
      (node (ref "R3") (pin "1") (pinfunction "A_1") (pintype "passive"))
      (node (ref "R4") (pin "1") (pinfunction "A_1") (pintype "passive"))
      (node (ref "STAB1") (pin "3") (pinfunction "GND_3") (pintype "passive"))
      (node (ref "U$1") (pin "P$1") (pinfunction "P$1_P$1") (pintype "bidirectional"))
      (node (ref "U$20") (pin "P$1") (pinfunction "P$1_P$1") (pintype "bidirectional"))
      (node (ref "ZOLD_3P1") (pin "1") (pinfunction "1_1") (pintype "passive"))
      (node (ref "ZOLD_3P10") (pin "1") (pinfunction "1_1") (pintype "passive"))
      (node (ref "ZOLD_3P11") (pin "1") (pinfunction "1_1") (pintype "passive"))
      (node (ref "ZOLD_3P12") (pin "1") (pinfunction "1_1") (pintype "passive"))
      (node (ref "ZOLD_3P2") (pin "1") (pinfunction "1_1") (pintype "passive"))
      (node (ref "ZOLD_3P3") (pin "1") (pinfunction "1_1") (pintype "passive"))
      (node (ref "ZOLD_3P4") (pin "1") (pinfunction "1_1") (pintype "passive"))
      (node (ref "ZOLD_3P5") (pin "1") (pinfunction "1_1") (pintype "passive"))
      (node (ref "ZOLD_3P6") (pin "1") (pinfunction "1_1") (pintype "passive"))
      (node (ref "ZOLD_3P7") (pin "1") (pinfunction "1_1") (pintype "passive"))
      (node (ref "ZOLD_3P8") (pin "1") (pinfunction "1_1") (pintype "passive"))
      (node (ref "ZOLD_3P9") (pin "1") (pinfunction "1_1") (pintype "passive"))
    )
    (net (code "4") (name "Net-(CANIC-CANH)") (class "Default")
      (node (ref "CANIC") (pin "7") (pinfunction "CANH_7") (pintype "bidirectional"))
      (node (ref "CN_CANLEZAR") (pin "2") (pinfunction "2_2") (pintype "passive"))
      (node (ref "CN_RJ1") (pin "5") (pinfunction "5_5") (pintype "passive"))
      (node (ref "CN_RJ2") (pin "5") (pinfunction "5_5") (pintype "passive"))
      (node (ref "U$1") (pin "P$2") (pinfunction "P$2_P$2") (pintype "bidirectional"))
    )
    (net (code "5") (name "Net-(CANIC-CANL)") (class "Default")
      (node (ref "CANIC") (pin "6") (pinfunction "CANL_6") (pintype "bidirectional"))
      (node (ref "CN_RJ1") (pin "4") (pinfunction "4_4") (pintype "passive"))
      (node (ref "CN_RJ2") (pin "4") (pinfunction "4_4") (pintype "passive"))
      (node (ref "R125") (pin "1") (pinfunction "A_1") (pintype "passive"))
      (node (ref "R126") (pin "2") (pinfunction "E_2") (pintype "passive"))
      (node (ref "U$1") (pin "P$3") (pinfunction "P$3_P$3") (pintype "bidirectional"))
    )
    (net (code "6") (name "Net-(CANIC-RXD)") (class "Default")
      (node (ref "CANIC") (pin "4") (pinfunction "RXD_4") (pintype "output"))
      (node (ref "PIC1") (pin "11") (pinfunction "RB3/CANRX_11") (pintype "bidirectional"))
    )
    (net (code "7") (name "Net-(CANIC-TXD)") (class "Default")
      (node (ref "CANIC") (pin "1") (pinfunction "TXD_1") (pintype "input"))
      (node (ref "PIC1") (pin "10") (pinfunction "RB2/INT2/CANTX_10") (pintype "bidirectional"))
    )
    (net (code "8") (name "Net-(CN3-Pad10)") (class "Default")
      (node (ref "CN3") (pin "10") (pinfunction "10_10") (pintype "passive"))
      (node (ref "CN3") (pin "9") (pinfunction "9_9") (pintype "passive"))
    )
    (net (code "9") (name "Net-(CN_RJ1-Pad7)") (class "Default")
      (node (ref "CN_RJ1") (pin "7") (pinfunction "7_7") (pintype "passive"))
      (node (ref "CN_RJ2") (pin "7") (pinfunction "7_7") (pintype "passive"))
      (node (ref "U$21") (pin "P$1") (pinfunction "P$1_P$1") (pintype "bidirectional"))
    )
    (net (code "10") (name "Net-(CN_RJ1-Pad8)") (class "Default")
      (node (ref "CN_RJ1") (pin "8") (pinfunction "8_8") (pintype "passive"))
      (node (ref "D2") (pin "C") (pinfunction "C_C") (pintype "passive"))
    )
    (net (code "11") (name "Net-(CN_RJ2-Pad8)") (class "Default")
      (node (ref "CN_RJ2") (pin "8") (pinfunction "8_8") (pintype "passive"))
      (node (ref "D1") (pin "C") (pinfunction "C_C") (pintype "passive"))
    )
    (net (code "12") (name "Net-(D1-PadA)") (class "Default")
      (node (ref "D1") (pin "A") (pinfunction "A_A") (pintype "passive"))
      (node (ref "D2") (pin "A") (pinfunction "A_A") (pintype "passive"))
      (node (ref "U$21") (pin "P$2") (pinfunction "P$2_P$2") (pintype "bidirectional"))
    )
    (net (code "13") (name "Net-(IC1-I{slash}O1)") (class "Default")
      (node (ref "C4") (pin "1") (pinfunction "1_1") (pintype "passive"))
      (node (ref "IC1") (pin "1") (pinfunction "I/O1_1") (pintype "bidirectional"))
      (node (ref "R101") (pin "2") (pinfunction "E_2") (pintype "passive"))
      (node (ref "R53") (pin "1") (pinfunction "A_1") (pintype "passive"))
    )
    (net (code "14") (name "Net-(IC1-I{slash}O2)") (class "Default")
      (node (ref "C5") (pin "1") (pinfunction "1_1") (pintype "passive"))
      (node (ref "IC1") (pin "3") (pinfunction "I/O2_3") (pintype "bidirectional"))
      (node (ref "R102") (pin "2") (pinfunction "E_2") (pintype "passive"))
      (node (ref "R54") (pin "1") (pinfunction "A_1") (pintype "passive"))
    )
    (net (code "15") (name "Net-(IC1-I{slash}O3)") (class "Default")
      (node (ref "C6") (pin "1") (pinfunction "1_1") (pintype "passive"))
      (node (ref "IC1") (pin "4") (pinfunction "I/O3_4") (pintype "bidirectional"))
      (node (ref "R103") (pin "2") (pinfunction "E_2") (pintype "passive"))
      (node (ref "R55") (pin "1") (pinfunction "A_1") (pintype "passive"))
    )
    (net (code "16") (name "Net-(IC1-I{slash}O4)") (class "Default")
      (node (ref "C7") (pin "1") (pinfunction "1_1") (pintype "passive"))
      (node (ref "IC1") (pin "6") (pinfunction "I/O4_6") (pintype "bidirectional"))
      (node (ref "R104") (pin "2") (pinfunction "E_2") (pintype "passive"))
      (node (ref "R56") (pin "1") (pinfunction "A_1") (pintype "passive"))
    )
    (net (code "17") (name "Net-(IC2-I{slash}O1)") (class "Default")
      (node (ref "C8") (pin "1") (pinfunction "1_1") (pintype "passive"))
      (node (ref "IC2") (pin "1") (pinfunction "I/O1_1") (pintype "bidirectional"))
      (node (ref "R105") (pin "2") (pinfunction "E_2") (pintype "passive"))
      (node (ref "R57") (pin "1") (pinfunction "A_1") (pintype "passive"))
    )
    (net (code "18") (name "Net-(IC2-I{slash}O2)") (class "Default")
      (node (ref "C9") (pin "1") (pinfunction "1_1") (pintype "passive"))
      (node (ref "IC2") (pin "3") (pinfunction "I/O2_3") (pintype "bidirectional"))
      (node (ref "R106") (pin "2") (pinfunction "E_2") (pintype "passive"))
      (node (ref "R58") (pin "1") (pinfunction "A_1") (pintype "passive"))
    )
    (net (code "19") (name "Net-(IC2-I{slash}O3)") (class "Default")
      (node (ref "C10") (pin "1") (pinfunction "1_1") (pintype "passive"))
      (node (ref "IC2") (pin "4") (pinfunction "I/O3_4") (pintype "bidirectional"))
      (node (ref "R107") (pin "2") (pinfunction "E_2") (pintype "passive"))
      (node (ref "R59") (pin "1") (pinfunction "A_1") (pintype "passive"))
    )
    (net (code "20") (name "Net-(IC2-I{slash}O4)") (class "Default")
      (node (ref "C11") (pin "1") (pinfunction "1_1") (pintype "passive"))
      (node (ref "IC2") (pin "6") (pinfunction "I/O4_6") (pintype "bidirectional"))
      (node (ref "R108") (pin "2") (pinfunction "E_2") (pintype "passive"))
      (node (ref "R60") (pin "1") (pinfunction "A_1") (pintype "passive"))
    )
    (net (code "21") (name "Net-(IC3-I{slash}O1)") (class "Default")
      (node (ref "C12") (pin "1") (pinfunction "1_1") (pintype "passive"))
      (node (ref "IC3") (pin "1") (pinfunction "I/O1_1") (pintype "bidirectional"))
      (node (ref "R109") (pin "2") (pinfunction "E_2") (pintype "passive"))
      (node (ref "R61") (pin "1") (pinfunction "A_1") (pintype "passive"))
    )
    (net (code "22") (name "Net-(IC3-I{slash}O2)") (class "Default")
      (node (ref "C13") (pin "1") (pinfunction "1_1") (pintype "passive"))
      (node (ref "IC3") (pin "3") (pinfunction "I/O2_3") (pintype "bidirectional"))
      (node (ref "R110") (pin "2") (pinfunction "E_2") (pintype "passive"))
      (node (ref "R62") (pin "1") (pinfunction "A_1") (pintype "passive"))
    )
    (net (code "23") (name "Net-(IC3-I{slash}O3)") (class "Default")
      (node (ref "C14") (pin "1") (pinfunction "1_1") (pintype "passive"))
      (node (ref "IC3") (pin "4") (pinfunction "I/O3_4") (pintype "bidirectional"))
      (node (ref "R111") (pin "2") (pinfunction "E_2") (pintype "passive"))
      (node (ref "R63") (pin "1") (pinfunction "A_1") (pintype "passive"))
    )
    (net (code "24") (name "Net-(IC3-I{slash}O4)") (class "Default")
      (node (ref "C15") (pin "1") (pinfunction "1_1") (pintype "passive"))
      (node (ref "IC3") (pin "6") (pinfunction "I/O4_6") (pintype "bidirectional"))
      (node (ref "R112") (pin "2") (pinfunction "E_2") (pintype "passive"))
      (node (ref "R64") (pin "1") (pinfunction "A_1") (pintype "passive"))
    )
    (net (code "25") (name "Net-(IC4-I{slash}O1)") (class "Default")
      (node (ref "C16") (pin "1") (pinfunction "1_1") (pintype "passive"))
      (node (ref "IC4") (pin "1") (pinfunction "I/O1_1") (pintype "bidirectional"))
      (node (ref "R113") (pin "2") (pinfunction "E_2") (pintype "passive"))
      (node (ref "R65") (pin "1") (pinfunction "A_1") (pintype "passive"))
    )
    (net (code "26") (name "Net-(IC4-I{slash}O2)") (class "Default")
      (node (ref "C17") (pin "1") (pinfunction "1_1") (pintype "passive"))
      (node (ref "IC4") (pin "3") (pinfunction "I/O2_3") (pintype "bidirectional"))
      (node (ref "R114") (pin "2") (pinfunction "E_2") (pintype "passive"))
      (node (ref "R66") (pin "1") (pinfunction "A_1") (pintype "passive"))
    )
    (net (code "27") (name "Net-(IC4-I{slash}O3)") (class "Default")
      (node (ref "C18") (pin "1") (pinfunction "1_1") (pintype "passive"))
      (node (ref "IC4") (pin "4") (pinfunction "I/O3_4") (pintype "bidirectional"))
      (node (ref "R115") (pin "2") (pinfunction "E_2") (pintype "passive"))
      (node (ref "R67") (pin "1") (pinfunction "A_1") (pintype "passive"))
    )
    (net (code "28") (name "Net-(IC4-I{slash}O4)") (class "Default")
      (node (ref "C19") (pin "1") (pinfunction "1_1") (pintype "passive"))
      (node (ref "IC4") (pin "6") (pinfunction "I/O4_6") (pintype "bidirectional"))
      (node (ref "R116") (pin "2") (pinfunction "E_2") (pintype "passive"))
      (node (ref "R68") (pin "1") (pinfunction "A_1") (pintype "passive"))
    )
    (net (code "29") (name "Net-(IC5-I{slash}O1)") (class "Default")
      (node (ref "C20") (pin "1") (pinfunction "1_1") (pintype "passive"))
      (node (ref "IC5") (pin "1") (pinfunction "I/O1_1") (pintype "bidirectional"))
      (node (ref "R117") (pin "2") (pinfunction "E_2") (pintype "passive"))
      (node (ref "R69") (pin "1") (pinfunction "A_1") (pintype "passive"))
    )
    (net (code "30") (name "Net-(IC5-I{slash}O2)") (class "Default")
      (node (ref "C21") (pin "1") (pinfunction "1_1") (pintype "passive"))
      (node (ref "IC5") (pin "3") (pinfunction "I/O2_3") (pintype "bidirectional"))
      (node (ref "R118") (pin "2") (pinfunction "E_2") (pintype "passive"))
      (node (ref "R70") (pin "1") (pinfunction "A_1") (pintype "passive"))
    )
    (net (code "31") (name "Net-(IC5-I{slash}O3)") (class "Default")
      (node (ref "C22") (pin "1") (pinfunction "1_1") (pintype "passive"))
      (node (ref "IC5") (pin "4") (pinfunction "I/O3_4") (pintype "bidirectional"))
      (node (ref "R119") (pin "2") (pinfunction "E_2") (pintype "passive"))
      (node (ref "R71") (pin "1") (pinfunction "A_1") (pintype "passive"))
    )
    (net (code "32") (name "Net-(IC5-I{slash}O4)") (class "Default")
      (node (ref "C23") (pin "1") (pinfunction "1_1") (pintype "passive"))
      (node (ref "IC5") (pin "6") (pinfunction "I/O4_6") (pintype "bidirectional"))
      (node (ref "R120") (pin "2") (pinfunction "E_2") (pintype "passive"))
      (node (ref "R72") (pin "1") (pinfunction "A_1") (pintype "passive"))
    )
    (net (code "33") (name "Net-(IC6-I{slash}O1)") (class "Default")
      (node (ref "C24") (pin "1") (pinfunction "1_1") (pintype "passive"))
      (node (ref "IC6") (pin "1") (pinfunction "I/O1_1") (pintype "bidirectional"))
      (node (ref "R121") (pin "2") (pinfunction "E_2") (pintype "passive"))
      (node (ref "R73") (pin "1") (pinfunction "A_1") (pintype "passive"))
    )
    (net (code "34") (name "Net-(IC6-I{slash}O2)") (class "Default")
      (node (ref "C25") (pin "1") (pinfunction "1_1") (pintype "passive"))
      (node (ref "IC6") (pin "3") (pinfunction "I/O2_3") (pintype "bidirectional"))
      (node (ref "R122") (pin "2") (pinfunction "E_2") (pintype "passive"))
      (node (ref "R74") (pin "1") (pinfunction "A_1") (pintype "passive"))
    )
    (net (code "35") (name "Net-(IC6-I{slash}O3)") (class "Default")
      (node (ref "C26") (pin "1") (pinfunction "1_1") (pintype "passive"))
      (node (ref "IC6") (pin "4") (pinfunction "I/O3_4") (pintype "bidirectional"))
      (node (ref "R123") (pin "2") (pinfunction "E_2") (pintype "passive"))
      (node (ref "R75") (pin "1") (pinfunction "A_1") (pintype "passive"))
    )
    (net (code "36") (name "Net-(IC6-I{slash}O4)") (class "Default")
      (node (ref "C27") (pin "1") (pinfunction "1_1") (pintype "passive"))
      (node (ref "IC6") (pin "6") (pinfunction "I/O4_6") (pintype "bidirectional"))
      (node (ref "R124") (pin "2") (pinfunction "E_2") (pintype "passive"))
      (node (ref "R76") (pin "1") (pinfunction "A_1") (pintype "passive"))
    )
    (net (code "37") (name "Net-(IC7-02_SDI)") (class "Default")
      (node (ref "IC7") (pin "2") (pinfunction "02_SDI_2") (pintype "input"))
      (node (ref "PIC1") (pin "43") (pinfunction "RC5/SDO_43") (pintype "bidirectional"))
    )
    (net (code "38") (name "Net-(IC7-03_CLK)") (class "Default")
      (node (ref "IC7") (pin "3") (pinfunction "03_CLK_3") (pintype "input"))
      (node (ref "IC8") (pin "3") (pinfunction "03_CLK_3") (pintype "input"))
      (node (ref "IC9") (pin "3") (pinfunction "03_CLK_3") (pintype "input"))
      (node (ref "PIC1") (pin "37") (pinfunction "RC3/SCK/SCL_37") (pintype "bidirectional"))
    )
    (net (code "39") (name "Net-(IC7-04_~{LA})") (class "Default")
      (node (ref "IC7") (pin "4") (pinfunction "04_~{LA}_4") (pintype "input"))
      (node (ref "IC8") (pin "4") (pinfunction "04_~{LA}_4") (pintype "input"))
      (node (ref "IC9") (pin "4") (pinfunction "04_~{LA}_4") (pintype "input"))
      (node (ref "PIC1") (pin "36") (pinfunction "RC2/CCP1_36") (pintype "bidirectional"))
    )
    (net (code "40") (name "Net-(IC7-05_OUT0)") (class "Default")
      (node (ref "IC7") (pin "5") (pinfunction "05_OUT0_5") (pintype "output"))
      (node (ref "R5") (pin "2") (pinfunction "E_2") (pintype "passive"))
      (node (ref "U5") (pin "P$1") (pinfunction "G_P$1") (pintype "passive"))
    )
    (net (code "41") (name "Net-(IC7-06_OUT1)") (class "Default")
      (node (ref "IC7") (pin "6") (pinfunction "06_OUT1_6") (pintype "output"))
      (node (ref "R6") (pin "2") (pinfunction "E_2") (pintype "passive"))
      (node (ref "U5") (pin "P$3") (pinfunction "G_P$3") (pintype "passive"))
    )
    (net (code "42") (name "Net-(IC7-07_OUT2)") (class "Default")
      (node (ref "IC7") (pin "7") (pinfunction "07_OUT2_7") (pintype "output"))
      (node (ref "R7") (pin "2") (pinfunction "E_2") (pintype "passive"))
      (node (ref "U6") (pin "P$1") (pinfunction "G_P$1") (pintype "passive"))
    )
    (net (code "43") (name "Net-(IC7-08_OUT3)") (class "Default")
      (node (ref "IC7") (pin "8") (pinfunction "08_OUT3_8") (pintype "output"))
      (node (ref "R8") (pin "2") (pinfunction "E_2") (pintype "passive"))
      (node (ref "U6") (pin "P$3") (pinfunction "G_P$3") (pintype "passive"))
    )
    (net (code "44") (name "Net-(IC7-09_OUT4)") (class "Default")
      (node (ref "IC7") (pin "9") (pinfunction "09_OUT4_9") (pintype "output"))
      (node (ref "R9") (pin "2") (pinfunction "E_2") (pintype "passive"))
      (node (ref "U7") (pin "P$1") (pinfunction "G_P$1") (pintype "passive"))
    )
    (net (code "45") (name "Net-(IC7-10_OUT5)") (class "Default")
      (node (ref "IC7") (pin "10") (pinfunction "10_OUT5_10") (pintype "output"))
      (node (ref "R10") (pin "2") (pinfunction "E_2") (pintype "passive"))
      (node (ref "U7") (pin "P$3") (pinfunction "G_P$3") (pintype "passive"))
    )
    (net (code "46") (name "Net-(IC7-11_OUT6)") (class "Default")
      (node (ref "IC7") (pin "11") (pinfunction "11_OUT6_11") (pintype "output"))
      (node (ref "R11") (pin "2") (pinfunction "E_2") (pintype "passive"))
      (node (ref "U8") (pin "P$1") (pinfunction "G_P$1") (pintype "passive"))
    )
    (net (code "47") (name "Net-(IC7-12_OUT7)") (class "Default")
      (node (ref "IC7") (pin "12") (pinfunction "12_OUT7_12") (pintype "output"))
      (node (ref "R12") (pin "2") (pinfunction "E_2") (pintype "passive"))
      (node (ref "U8") (pin "P$3") (pinfunction "G_P$3") (pintype "passive"))
    )
    (net (code "48") (name "Net-(IC7-14_SDO)") (class "Default")
      (node (ref "IC7") (pin "14") (pinfunction "14_SDO_14") (pintype "output"))
      (node (ref "IC8") (pin "2") (pinfunction "02_SDI_2") (pintype "input"))
    )
    (net (code "49") (name "Net-(IC7-15_REXT)") (class "Default")
      (node (ref "IC7") (pin "15") (pinfunction "15_REXT_15") (pintype "bidirectional"))
      (node (ref "R2") (pin "2") (pinfunction "E_2") (pintype "passive"))
    )
    (net (code "50") (name "Net-(IC8-05_OUT0)") (class "Default")
      (node (ref "IC8") (pin "5") (pinfunction "05_OUT0_5") (pintype "output"))
      (node (ref "R13") (pin "2") (pinfunction "E_2") (pintype "passive"))
      (node (ref "U9") (pin "P$1") (pinfunction "G_P$1") (pintype "passive"))
    )
    (net (code "51") (name "Net-(IC8-06_OUT1)") (class "Default")
      (node (ref "IC8") (pin "6") (pinfunction "06_OUT1_6") (pintype "output"))
      (node (ref "R14") (pin "2") (pinfunction "E_2") (pintype "passive"))
      (node (ref "U9") (pin "P$3") (pinfunction "G_P$3") (pintype "passive"))
    )
    (net (code "52") (name "Net-(IC8-07_OUT2)") (class "Default")
      (node (ref "IC8") (pin "7") (pinfunction "07_OUT2_7") (pintype "output"))
      (node (ref "R15") (pin "2") (pinfunction "E_2") (pintype "passive"))
      (node (ref "U10") (pin "P$1") (pinfunction "G_P$1") (pintype "passive"))
    )
    (net (code "53") (name "Net-(IC8-08_OUT3)") (class "Default")
      (node (ref "IC8") (pin "8") (pinfunction "08_OUT3_8") (pintype "output"))
      (node (ref "R16") (pin "2") (pinfunction "E_2") (pintype "passive"))
      (node (ref "U10") (pin "P$3") (pinfunction "G_P$3") (pintype "passive"))
    )
    (net (code "54") (name "Net-(IC8-09_OUT4)") (class "Default")
      (node (ref "IC8") (pin "9") (pinfunction "09_OUT4_9") (pintype "output"))
      (node (ref "R17") (pin "2") (pinfunction "E_2") (pintype "passive"))
      (node (ref "U11") (pin "P$1") (pinfunction "G_P$1") (pintype "passive"))
    )
    (net (code "55") (name "Net-(IC8-10_OUT5)") (class "Default")
      (node (ref "IC8") (pin "10") (pinfunction "10_OUT5_10") (pintype "output"))
      (node (ref "R18") (pin "2") (pinfunction "E_2") (pintype "passive"))
      (node (ref "U11") (pin "P$3") (pinfunction "G_P$3") (pintype "passive"))
    )
    (net (code "56") (name "Net-(IC8-11_OUT6)") (class "Default")
      (node (ref "IC8") (pin "11") (pinfunction "11_OUT6_11") (pintype "output"))
      (node (ref "R19") (pin "2") (pinfunction "E_2") (pintype "passive"))
      (node (ref "U12") (pin "P$1") (pinfunction "G_P$1") (pintype "passive"))
    )
    (net (code "57") (name "Net-(IC8-12_OUT7)") (class "Default")
      (node (ref "IC8") (pin "12") (pinfunction "12_OUT7_12") (pintype "output"))
      (node (ref "R20") (pin "2") (pinfunction "E_2") (pintype "passive"))
      (node (ref "U12") (pin "P$3") (pinfunction "G_P$3") (pintype "passive"))
    )
    (net (code "58") (name "Net-(IC8-14_SDO)") (class "Default")
      (node (ref "IC8") (pin "14") (pinfunction "14_SDO_14") (pintype "output"))
      (node (ref "IC9") (pin "2") (pinfunction "02_SDI_2") (pintype "input"))
    )
    (net (code "59") (name "Net-(IC8-15_REXT)") (class "Default")
      (node (ref "IC8") (pin "15") (pinfunction "15_REXT_15") (pintype "bidirectional"))
      (node (ref "R3") (pin "2") (pinfunction "E_2") (pintype "passive"))
    )
    (net (code "60") (name "Net-(IC9-05_OUT0)") (class "Default")
      (node (ref "IC9") (pin "5") (pinfunction "05_OUT0_5") (pintype "output"))
      (node (ref "R21") (pin "2") (pinfunction "E_2") (pintype "passive"))
      (node (ref "U13") (pin "P$1") (pinfunction "G_P$1") (pintype "passive"))
    )
    (net (code "61") (name "Net-(IC9-06_OUT1)") (class "Default")
      (node (ref "IC9") (pin "6") (pinfunction "06_OUT1_6") (pintype "output"))
      (node (ref "R22") (pin "2") (pinfunction "E_2") (pintype "passive"))
      (node (ref "U13") (pin "P$3") (pinfunction "G_P$3") (pintype "passive"))
    )
    (net (code "62") (name "Net-(IC9-07_OUT2)") (class "Default")
      (node (ref "IC9") (pin "7") (pinfunction "07_OUT2_7") (pintype "output"))
      (node (ref "R23") (pin "2") (pinfunction "E_2") (pintype "passive"))
      (node (ref "U14") (pin "P$1") (pinfunction "G_P$1") (pintype "passive"))
    )
    (net (code "63") (name "Net-(IC9-08_OUT3)") (class "Default")
      (node (ref "IC9") (pin "8") (pinfunction "08_OUT3_8") (pintype "output"))
      (node (ref "R24") (pin "2") (pinfunction "E_2") (pintype "passive"))
      (node (ref "U14") (pin "P$3") (pinfunction "G_P$3") (pintype "passive"))
    )
    (net (code "64") (name "Net-(IC9-09_OUT4)") (class "Default")
      (node (ref "IC9") (pin "9") (pinfunction "09_OUT4_9") (pintype "output"))
      (node (ref "R25") (pin "2") (pinfunction "E_2") (pintype "passive"))
      (node (ref "U15") (pin "P$1") (pinfunction "G_P$1") (pintype "passive"))
    )
    (net (code "65") (name "Net-(IC9-10_OUT5)") (class "Default")
      (node (ref "IC9") (pin "10") (pinfunction "10_OUT5_10") (pintype "output"))
      (node (ref "R26") (pin "2") (pinfunction "E_2") (pintype "passive"))
      (node (ref "U15") (pin "P$3") (pinfunction "G_P$3") (pintype "passive"))
    )
    (net (code "66") (name "Net-(IC9-11_OUT6)") (class "Default")
      (node (ref "IC9") (pin "11") (pinfunction "11_OUT6_11") (pintype "output"))
      (node (ref "R27") (pin "2") (pinfunction "E_2") (pintype "passive"))
      (node (ref "U16") (pin "P$1") (pinfunction "G_P$1") (pintype "passive"))
    )
    (net (code "67") (name "Net-(IC9-12_OUT7)") (class "Default")
      (node (ref "IC9") (pin "12") (pinfunction "12_OUT7_12") (pintype "output"))
      (node (ref "R28") (pin "2") (pinfunction "E_2") (pintype "passive"))
      (node (ref "U16") (pin "P$3") (pinfunction "G_P$3") (pintype "passive"))
    )
    (net (code "68") (name "Net-(IC9-15_REXT)") (class "Default")
      (node (ref "IC9") (pin "15") (pinfunction "15_REXT_15") (pintype "bidirectional"))
      (node (ref "R4") (pin "2") (pinfunction "E_2") (pintype "passive"))
    )
    (net (code "69") (name "Net-(PIC1-OSC1{slash}CLKI{slash}RA7)") (class "Default")
      (node (ref "C2") (pin "1") (pinfunction "1_1") (pintype "passive"))
      (node (ref "PIC1") (pin "30") (pinfunction "OSC1/CLKI/RA7_30") (pintype "bidirectional"))
      (node (ref "Q1") (pin "1") (pinfunction "1_1") (pintype "passive"))
    )
    (net (code "70") (name "Net-(PIC1-OSC2{slash}CLKO{slash}RA6)") (class "Default")
      (node (ref "C1") (pin "1") (pinfunction "1_1") (pintype "passive"))
      (node (ref "PIC1") (pin "31") (pinfunction "OSC2/CLKO/RA6_31") (pintype "bidirectional"))
      (node (ref "Q1") (pin "2") (pinfunction "2_2") (pintype "passive"))
    )
    (net (code "71") (name "Net-(PIC1-RA0{slash}AN0{slash}CVREF)") (class "Default")
      (node (ref "PIC1") (pin "19") (pinfunction "RA0/AN0/CVREF_19") (pintype "bidirectional"))
      (node (ref "R112") (pin "1") (pinfunction "A_1") (pintype "passive"))
    )
    (net (code "72") (name "Net-(PIC1-RA1{slash}AN1)") (class "Default")
      (node (ref "PIC1") (pin "20") (pinfunction "RA1/AN1_20") (pintype "bidirectional"))
      (node (ref "R113") (pin "1") (pinfunction "A_1") (pintype "passive"))
    )
    (net (code "73") (name "Net-(PIC1-RA2{slash}AN2{slash}VREF-)") (class "Default")
      (node (ref "PIC1") (pin "21") (pinfunction "RA2/AN2/VREF-_21") (pintype "bidirectional"))
      (node (ref "R107") (pin "1") (pinfunction "A_1") (pintype "passive"))
    )
    (net (code "74") (name "Net-(PIC1-RA3{slash}AN3{slash}VREF+)") (class "Default")
      (node (ref "PIC1") (pin "22") (pinfunction "RA3/AN3/VREF+_22") (pintype "bidirectional"))
      (node (ref "R116") (pin "1") (pinfunction "A_1") (pintype "passive"))
    )
    (net (code "75") (name "Net-(PIC1-RA5{slash}AN4{slash}~{SS{slash}HLVDIN})") (class "Default")
      (node (ref "PIC1") (pin "24") (pinfunction "RA5/AN4/~{SS/HLVDIN}_24") (pintype "bidirectional"))
      (node (ref "R108") (pin "1") (pinfunction "A_1") (pintype "passive"))
    )
    (net (code "76") (name "Net-(PIC1-RB0{slash}INT0{slash}FLT0{slash}AN10)") (class "Default")
      (node (ref "PIC1") (pin "8") (pinfunction "RB0/INT0/FLT0/AN10_8") (pintype "bidirectional"))
      (node (ref "R122") (pin "1") (pinfunction "A_1") (pintype "passive"))
    )
    (net (code "77") (name "Net-(PIC1-RB1{slash}INT1{slash}AN8)") (class "Default")
      (node (ref "PIC1") (pin "9") (pinfunction "RB1/INT1/AN8_9") (pintype "bidirectional"))
      (node (ref "R123") (pin "1") (pinfunction "A_1") (pintype "passive"))
    )
    (net (code "78") (name "Net-(PIC1-RB4{slash}KBI0{slash}AN9)") (class "Default")
      (node (ref "PIC1") (pin "14") (pinfunction "RB4/KBI0/AN9_14") (pintype "bidirectional"))
      (node (ref "R124") (pin "1") (pinfunction "A_1") (pintype "passive"))
    )
    (net (code "79") (name "Net-(PIC1-RB5{slash}KBI1{slash}PGM)") (class "Default")
      (node (ref "PIC1") (pin "15") (pinfunction "RB5/KBI1/PGM_15") (pintype "bidirectional"))
      (node (ref "R109") (pin "1") (pinfunction "A_1") (pintype "passive"))
    )
    (net (code "80") (name "Net-(PIC1-RB6{slash}KBI2{slash}PGC)") (class "Default")
      (node (ref "CN3") (pin "5") (pinfunction "5_5") (pintype "passive"))
      (node (ref "CN3") (pin "6") (pinfunction "6_6") (pintype "passive"))
      (node (ref "CN_TANIT") (pin "5") (pinfunction "5_5") (pintype "passive"))
      (node (ref "PIC1") (pin "16") (pinfunction "RB6/KBI2/PGC_16") (pintype "bidirectional"))
    )
    (net (code "81") (name "Net-(PIC1-RB7{slash}KBI3{slash}PGD)") (class "Default")
      (node (ref "CN3") (pin "7") (pinfunction "7_7") (pintype "passive"))
      (node (ref "CN3") (pin "8") (pinfunction "8_8") (pintype "passive"))
      (node (ref "CN_TANIT") (pin "4") (pinfunction "4_4") (pintype "passive"))
      (node (ref "PIC1") (pin "17") (pinfunction "RB7/KBI3/PGD_17") (pintype "bidirectional"))
    )
    (net (code "82") (name "Net-(PIC1-RC0{slash}T1OSO{slash}T13CKI)") (class "Default")
      (node (ref "PIC1") (pin "32") (pinfunction "RC0/T1OSO/T13CKI_32") (pintype "bidirectional"))
      (node (ref "R114") (pin "1") (pinfunction "A_1") (pintype "passive"))
    )
    (net (code "83") (name "Net-(PIC1-RC1{slash}T1OSI)") (class "Default")
      (node (ref "PIC1") (pin "35") (pinfunction "RC1/T1OSI_35") (pintype "bidirectional"))
      (node (ref "R115") (pin "1") (pinfunction "A_1") (pintype "passive"))
    )
    (net (code "84") (name "Net-(PIC1-RC4{slash}SDI{slash}SDA)") (class "Default")
      (node (ref "PIC1") (pin "42") (pinfunction "RC4/SDI/SDA_42") (pintype "bidirectional"))
      (node (ref "R102") (pin "1") (pinfunction "A_1") (pintype "passive"))
    )
    (net (code "85") (name "Net-(PIC1-RC6{slash}TX{slash}CK)") (class "Default")
      (node (ref "PIC1") (pin "44") (pinfunction "RC6/TX/CK_44") (pintype "bidirectional"))
      (node (ref "R101") (pin "1") (pinfunction "A_1") (pintype "passive"))
    )
    (net (code "86") (name "Net-(PIC1-RC7{slash}RX{slash}DT)") (class "Default")
      (node (ref "PIC1") (pin "1") (pinfunction "RC7/RX/DT_1") (pintype "bidirectional"))
      (node (ref "R117") (pin "1") (pinfunction "A_1") (pintype "passive"))
    )
    (net (code "87") (name "Net-(PIC1-RD0{slash}PSP0{slash}C1IN+)") (class "Default")
      (node (ref "PIC1") (pin "38") (pinfunction "RD0/PSP0/C1IN+_38") (pintype "bidirectional"))
      (node (ref "R104") (pin "1") (pinfunction "A_1") (pintype "passive"))
    )
    (net (code "88") (name "Net-(PIC1-RD1{slash}PSP1{slash}C1IN-)") (class "Default")
      (node (ref "PIC1") (pin "39") (pinfunction "RD1/PSP1/C1IN-_39") (pintype "bidirectional"))
      (node (ref "R103") (pin "1") (pinfunction "A_1") (pintype "passive"))
    )
    (net (code "89") (name "Net-(PIC1-RD2{slash}PSP2{slash}C2IN+)") (class "Default")
      (node (ref "PIC1") (pin "40") (pinfunction "RD2/PSP2/C2IN+_40") (pintype "bidirectional"))
      (node (ref "R111") (pin "1") (pinfunction "A_1") (pintype "passive"))
    )
    (net (code "90") (name "Net-(PIC1-RD3{slash}PSP3{slash}C2IN-)") (class "Default")
      (node (ref "PIC1") (pin "41") (pinfunction "RD3/PSP3/C2IN-_41") (pintype "bidirectional"))
      (node (ref "R110") (pin "1") (pinfunction "A_1") (pintype "passive"))
    )
    (net (code "91") (name "Net-(PIC1-RD4{slash}PSP4{slash}ECCP1{slash}P1A)") (class "Default")
      (node (ref "PIC1") (pin "2") (pinfunction "RD4/PSP4/ECCP1/P1A_2") (pintype "bidirectional"))
      (node (ref "R118") (pin "1") (pinfunction "A_1") (pintype "passive"))
    )
    (net (code "92") (name "Net-(PIC1-RD5{slash}PSP5{slash}P1B)") (class "Default")
      (node (ref "PIC1") (pin "3") (pinfunction "RD5/PSP5/P1B_3") (pintype "bidirectional"))
      (node (ref "R119") (pin "1") (pinfunction "A_1") (pintype "passive"))
    )
    (net (code "93") (name "Net-(PIC1-RD6{slash}PSP6{slash}P1C)") (class "Default")
      (node (ref "PIC1") (pin "4") (pinfunction "RD6/PSP6/P1C_4") (pintype "bidirectional"))
      (node (ref "R120") (pin "1") (pinfunction "A_1") (pintype "passive"))
    )
    (net (code "94") (name "Net-(PIC1-RD7{slash}PSP7{slash}P1D)") (class "Default")
      (node (ref "PIC1") (pin "5") (pinfunction "RD7/PSP7/P1D_5") (pintype "bidirectional"))
      (node (ref "R121") (pin "1") (pinfunction "A_1") (pintype "passive"))
    )
    (net (code "95") (name "Net-(PIC1-RE1{slash}~{WR{slash}AN6{slash}C1OUT})") (class "Default")
      (node (ref "PIC1") (pin "26") (pinfunction "RE1/~{WR/AN6/C1OUT}_26") (pintype "bidirectional"))
      (node (ref "R106") (pin "1") (pinfunction "A_1") (pintype "passive"))
    )
    (net (code "96") (name "Net-(PIC1-RE2{slash}~{CS{slash}AN7{slash}C2OUT})") (class "Default")
      (node (ref "PIC1") (pin "27") (pinfunction "RE2/~{CS/AN7/C2OUT}_27") (pintype "bidirectional"))
      (node (ref "R105") (pin "1") (pinfunction "A_1") (pintype "passive"))
    )
    (net (code "97") (name "Net-(PIC1-VDDCORE{slash}VCAP)") (class "Default")
      (node (ref "C3") (pin "1") (pinfunction "1_1") (pintype "passive"))
      (node (ref "PIC1") (pin "23") (pinfunction "VDDCORE/VCAP_23") (pintype "bidirectional"))
    )
    (net (code "98") (name "Net-(PIC1-~{MCLR{slash}VPP{slash}RE3})") (class "Default")
      (node (ref "CN_TANIT") (pin "3") (pinfunction "3_3") (pintype "passive"))
      (node (ref "PIC1") (pin "18") (pinfunction "~{MCLR/VPP/RE3}_18") (pintype "input"))
      (node (ref "R1") (pin "1") (pinfunction "A_1") (pintype "passive"))
    )
    (net (code "99") (name "Net-(R29-A)") (class "Default")
      (node (ref "R29") (pin "1") (pinfunction "A_1") (pintype "passive"))
      (node (ref "R53") (pin "2") (pinfunction "E_2") (pintype "passive"))
      (node (ref "R77") (pin "2") (pinfunction "E_2") (pintype "passive"))
      (node (ref "ZOLD_3P1") (pin "2") (pinfunction "1_2") (pintype "passive"))
    )
    (net (code "100") (name "Net-(R29-E)") (class "Default")
      (node (ref "R29") (pin "2") (pinfunction "E_2") (pintype "passive"))
      (node (ref "U5") (pin "P$6") (pinfunction "D_P$6") (pintype "passive"))
    )
    (net (code "101") (name "Net-(R30-A)") (class "Default")
      (node (ref "R30") (pin "1") (pinfunction "A_1") (pintype "passive"))
      (node (ref "R54") (pin "2") (pinfunction "E_2") (pintype "passive"))
      (node (ref "R78") (pin "2") (pinfunction "E_2") (pintype "passive"))
      (node (ref "ZOLD_3P1") (pin "3") (pinfunction "1_3") (pintype "passive"))
    )
    (net (code "102") (name "Net-(R30-E)") (class "Default")
      (node (ref "R30") (pin "2") (pinfunction "E_2") (pintype "passive"))
      (node (ref "U5") (pin "P$4") (pinfunction "D_P$4") (pintype "passive"))
    )
    (net (code "103") (name "Net-(R31-A)") (class "Default")
      (node (ref "R31") (pin "1") (pinfunction "A_1") (pintype "passive"))
      (node (ref "R55") (pin "2") (pinfunction "E_2") (pintype "passive"))
      (node (ref "R79") (pin "2") (pinfunction "E_2") (pintype "passive"))
      (node (ref "ZOLD_3P2") (pin "2") (pinfunction "1_2") (pintype "passive"))
    )
    (net (code "104") (name "Net-(R31-E)") (class "Default")
      (node (ref "R31") (pin "2") (pinfunction "E_2") (pintype "passive"))
      (node (ref "U6") (pin "P$6") (pinfunction "D_P$6") (pintype "passive"))
    )
    (net (code "105") (name "Net-(R32-A)") (class "Default")
      (node (ref "R32") (pin "1") (pinfunction "A_1") (pintype "passive"))
      (node (ref "R56") (pin "2") (pinfunction "E_2") (pintype "passive"))
      (node (ref "R80") (pin "2") (pinfunction "E_2") (pintype "passive"))
      (node (ref "ZOLD_3P2") (pin "3") (pinfunction "1_3") (pintype "passive"))
    )
    (net (code "106") (name "Net-(R32-E)") (class "Default")
      (node (ref "R32") (pin "2") (pinfunction "E_2") (pintype "passive"))
      (node (ref "U6") (pin "P$4") (pinfunction "D_P$4") (pintype "passive"))
    )
    (net (code "107") (name "Net-(R33-A)") (class "Default")
      (node (ref "R33") (pin "1") (pinfunction "A_1") (pintype "passive"))
      (node (ref "R57") (pin "2") (pinfunction "E_2") (pintype "passive"))
      (node (ref "R81") (pin "2") (pinfunction "E_2") (pintype "passive"))
      (node (ref "ZOLD_3P3") (pin "2") (pinfunction "1_2") (pintype "passive"))
    )
    (net (code "108") (name "Net-(R33-E)") (class "Default")
      (node (ref "R33") (pin "2") (pinfunction "E_2") (pintype "passive"))
      (node (ref "U7") (pin "P$6") (pinfunction "D_P$6") (pintype "passive"))
    )
    (net (code "109") (name "Net-(R34-A)") (class "Default")
      (node (ref "R34") (pin "1") (pinfunction "A_1") (pintype "passive"))
      (node (ref "R58") (pin "2") (pinfunction "E_2") (pintype "passive"))
      (node (ref "R82") (pin "2") (pinfunction "E_2") (pintype "passive"))
      (node (ref "ZOLD_3P3") (pin "3") (pinfunction "1_3") (pintype "passive"))
    )
    (net (code "110") (name "Net-(R34-E)") (class "Default")
      (node (ref "R34") (pin "2") (pinfunction "E_2") (pintype "passive"))
      (node (ref "U7") (pin "P$4") (pinfunction "D_P$4") (pintype "passive"))
    )
    (net (code "111") (name "Net-(R35-A)") (class "Default")
      (node (ref "R35") (pin "1") (pinfunction "A_1") (pintype "passive"))
      (node (ref "R59") (pin "2") (pinfunction "E_2") (pintype "passive"))
      (node (ref "R83") (pin "2") (pinfunction "E_2") (pintype "passive"))
      (node (ref "ZOLD_3P4") (pin "2") (pinfunction "1_2") (pintype "passive"))
    )
    (net (code "112") (name "Net-(R35-E)") (class "Default")
      (node (ref "R35") (pin "2") (pinfunction "E_2") (pintype "passive"))
      (node (ref "U8") (pin "P$6") (pinfunction "D_P$6") (pintype "passive"))
    )
    (net (code "113") (name "Net-(R36-A)") (class "Default")
      (node (ref "R36") (pin "1") (pinfunction "A_1") (pintype "passive"))
      (node (ref "R60") (pin "2") (pinfunction "E_2") (pintype "passive"))
      (node (ref "R84") (pin "2") (pinfunction "E_2") (pintype "passive"))
      (node (ref "ZOLD_3P4") (pin "3") (pinfunction "1_3") (pintype "passive"))
    )
    (net (code "114") (name "Net-(R36-E)") (class "Default")
      (node (ref "R36") (pin "2") (pinfunction "E_2") (pintype "passive"))
      (node (ref "U8") (pin "P$4") (pinfunction "D_P$4") (pintype "passive"))
    )
    (net (code "115") (name "Net-(R37-A)") (class "Default")
      (node (ref "R37") (pin "1") (pinfunction "A_1") (pintype "passive"))
      (node (ref "R61") (pin "2") (pinfunction "E_2") (pintype "passive"))
      (node (ref "R85") (pin "2") (pinfunction "E_2") (pintype "passive"))
      (node (ref "ZOLD_3P5") (pin "2") (pinfunction "1_2") (pintype "passive"))
    )
    (net (code "116") (name "Net-(R37-E)") (class "Default")
      (node (ref "R37") (pin "2") (pinfunction "E_2") (pintype "passive"))
      (node (ref "U9") (pin "P$6") (pinfunction "D_P$6") (pintype "passive"))
    )
    (net (code "117") (name "Net-(R38-A)") (class "Default")
      (node (ref "R38") (pin "1") (pinfunction "A_1") (pintype "passive"))
      (node (ref "R62") (pin "2") (pinfunction "E_2") (pintype "passive"))
      (node (ref "R86") (pin "2") (pinfunction "E_2") (pintype "passive"))
      (node (ref "ZOLD_3P5") (pin "3") (pinfunction "1_3") (pintype "passive"))
    )
    (net (code "118") (name "Net-(R38-E)") (class "Default")
      (node (ref "R38") (pin "2") (pinfunction "E_2") (pintype "passive"))
      (node (ref "U9") (pin "P$4") (pinfunction "D_P$4") (pintype "passive"))
    )
    (net (code "119") (name "Net-(R39-A)") (class "Default")
      (node (ref "R39") (pin "1") (pinfunction "A_1") (pintype "passive"))
      (node (ref "R63") (pin "2") (pinfunction "E_2") (pintype "passive"))
      (node (ref "R87") (pin "2") (pinfunction "E_2") (pintype "passive"))
      (node (ref "ZOLD_3P6") (pin "2") (pinfunction "1_2") (pintype "passive"))
    )
    (net (code "120") (name "Net-(R39-E)") (class "Default")
      (node (ref "R39") (pin "2") (pinfunction "E_2") (pintype "passive"))
      (node (ref "U10") (pin "P$6") (pinfunction "D_P$6") (pintype "passive"))
    )
    (net (code "121") (name "Net-(R40-A)") (class "Default")
      (node (ref "R40") (pin "1") (pinfunction "A_1") (pintype "passive"))
      (node (ref "R64") (pin "2") (pinfunction "E_2") (pintype "passive"))
      (node (ref "R88") (pin "2") (pinfunction "E_2") (pintype "passive"))
      (node (ref "ZOLD_3P6") (pin "3") (pinfunction "1_3") (pintype "passive"))
    )
    (net (code "122") (name "Net-(R40-E)") (class "Default")
      (node (ref "R40") (pin "2") (pinfunction "E_2") (pintype "passive"))
      (node (ref "U10") (pin "P$4") (pinfunction "D_P$4") (pintype "passive"))
    )
    (net (code "123") (name "Net-(R41-A)") (class "Default")
      (node (ref "R41") (pin "1") (pinfunction "A_1") (pintype "passive"))
      (node (ref "R65") (pin "2") (pinfunction "E_2") (pintype "passive"))
      (node (ref "R89") (pin "2") (pinfunction "E_2") (pintype "passive"))
      (node (ref "ZOLD_3P7") (pin "2") (pinfunction "1_2") (pintype "passive"))
    )
    (net (code "124") (name "Net-(R41-E)") (class "Default")
      (node (ref "R41") (pin "2") (pinfunction "E_2") (pintype "passive"))
      (node (ref "U11") (pin "P$6") (pinfunction "D_P$6") (pintype "passive"))
    )
    (net (code "125") (name "Net-(R42-A)") (class "Default")
      (node (ref "R42") (pin "1") (pinfunction "A_1") (pintype "passive"))
      (node (ref "R66") (pin "2") (pinfunction "E_2") (pintype "passive"))
      (node (ref "R90") (pin "2") (pinfunction "E_2") (pintype "passive"))
      (node (ref "ZOLD_3P7") (pin "3") (pinfunction "1_3") (pintype "passive"))
    )
    (net (code "126") (name "Net-(R42-E)") (class "Default")
      (node (ref "R42") (pin "2") (pinfunction "E_2") (pintype "passive"))
      (node (ref "U11") (pin "P$4") (pinfunction "D_P$4") (pintype "passive"))
    )
    (net (code "127") (name "Net-(R43-A)") (class "Default")
      (node (ref "R43") (pin "1") (pinfunction "A_1") (pintype "passive"))
      (node (ref "R67") (pin "2") (pinfunction "E_2") (pintype "passive"))
      (node (ref "R91") (pin "2") (pinfunction "E_2") (pintype "passive"))
      (node (ref "ZOLD_3P8") (pin "2") (pinfunction "1_2") (pintype "passive"))
    )
    (net (code "128") (name "Net-(R43-E)") (class "Default")
      (node (ref "R43") (pin "2") (pinfunction "E_2") (pintype "passive"))
      (node (ref "U12") (pin "P$6") (pinfunction "D_P$6") (pintype "passive"))
    )
    (net (code "129") (name "Net-(R44-A)") (class "Default")
      (node (ref "R44") (pin "1") (pinfunction "A_1") (pintype "passive"))
      (node (ref "R68") (pin "2") (pinfunction "E_2") (pintype "passive"))
      (node (ref "R92") (pin "2") (pinfunction "E_2") (pintype "passive"))
      (node (ref "ZOLD_3P8") (pin "3") (pinfunction "1_3") (pintype "passive"))
    )
    (net (code "130") (name "Net-(R44-E)") (class "Default")
      (node (ref "R44") (pin "2") (pinfunction "E_2") (pintype "passive"))
      (node (ref "U12") (pin "P$4") (pinfunction "D_P$4") (pintype "passive"))
    )
    (net (code "131") (name "Net-(R45-A)") (class "Default")
      (node (ref "R45") (pin "1") (pinfunction "A_1") (pintype "passive"))
      (node (ref "R69") (pin "2") (pinfunction "E_2") (pintype "passive"))
      (node (ref "R93") (pin "2") (pinfunction "E_2") (pintype "passive"))
      (node (ref "ZOLD_3P9") (pin "2") (pinfunction "1_2") (pintype "passive"))
    )
    (net (code "132") (name "Net-(R45-E)") (class "Default")
      (node (ref "R45") (pin "2") (pinfunction "E_2") (pintype "passive"))
      (node (ref "U13") (pin "P$6") (pinfunction "D_P$6") (pintype "passive"))
    )
    (net (code "133") (name "Net-(R46-A)") (class "Default")
      (node (ref "R46") (pin "1") (pinfunction "A_1") (pintype "passive"))
      (node (ref "R70") (pin "2") (pinfunction "E_2") (pintype "passive"))
      (node (ref "R94") (pin "2") (pinfunction "E_2") (pintype "passive"))
      (node (ref "ZOLD_3P9") (pin "3") (pinfunction "1_3") (pintype "passive"))
    )
    (net (code "134") (name "Net-(R46-E)") (class "Default")
      (node (ref "R46") (pin "2") (pinfunction "E_2") (pintype "passive"))
      (node (ref "U13") (pin "P$4") (pinfunction "D_P$4") (pintype "passive"))
    )
    (net (code "135") (name "Net-(R47-A)") (class "Default")
      (node (ref "R47") (pin "1") (pinfunction "A_1") (pintype "passive"))
      (node (ref "R71") (pin "2") (pinfunction "E_2") (pintype "passive"))
      (node (ref "R95") (pin "2") (pinfunction "E_2") (pintype "passive"))
      (node (ref "ZOLD_3P10") (pin "2") (pinfunction "1_2") (pintype "passive"))
    )
    (net (code "136") (name "Net-(R47-E)") (class "Default")
      (node (ref "R47") (pin "2") (pinfunction "E_2") (pintype "passive"))
      (node (ref "U14") (pin "P$6") (pinfunction "D_P$6") (pintype "passive"))
    )
    (net (code "137") (name "Net-(R48-A)") (class "Default")
      (node (ref "R48") (pin "1") (pinfunction "A_1") (pintype "passive"))
      (node (ref "R72") (pin "2") (pinfunction "E_2") (pintype "passive"))
      (node (ref "R96") (pin "2") (pinfunction "E_2") (pintype "passive"))
      (node (ref "ZOLD_3P10") (pin "3") (pinfunction "1_3") (pintype "passive"))
    )
    (net (code "138") (name "Net-(R48-E)") (class "Default")
      (node (ref "R48") (pin "2") (pinfunction "E_2") (pintype "passive"))
      (node (ref "U14") (pin "P$4") (pinfunction "D_P$4") (pintype "passive"))
    )
    (net (code "139") (name "Net-(R49-A)") (class "Default")
      (node (ref "R49") (pin "1") (pinfunction "A_1") (pintype "passive"))
      (node (ref "R73") (pin "2") (pinfunction "E_2") (pintype "passive"))
      (node (ref "R97") (pin "2") (pinfunction "E_2") (pintype "passive"))
      (node (ref "ZOLD_3P11") (pin "2") (pinfunction "1_2") (pintype "passive"))
    )
    (net (code "140") (name "Net-(R49-E)") (class "Default")
      (node (ref "R49") (pin "2") (pinfunction "E_2") (pintype "passive"))
      (node (ref "U15") (pin "P$6") (pinfunction "D_P$6") (pintype "passive"))
    )
    (net (code "141") (name "Net-(R50-A)") (class "Default")
      (node (ref "R50") (pin "1") (pinfunction "A_1") (pintype "passive"))
      (node (ref "R74") (pin "2") (pinfunction "E_2") (pintype "passive"))
      (node (ref "R98") (pin "2") (pinfunction "E_2") (pintype "passive"))
      (node (ref "ZOLD_3P11") (pin "3") (pinfunction "1_3") (pintype "passive"))
    )
    (net (code "142") (name "Net-(R50-E)") (class "Default")
      (node (ref "R50") (pin "2") (pinfunction "E_2") (pintype "passive"))
      (node (ref "U15") (pin "P$4") (pinfunction "D_P$4") (pintype "passive"))
    )
    (net (code "143") (name "Net-(R51-A)") (class "Default")
      (node (ref "R51") (pin "1") (pinfunction "A_1") (pintype "passive"))
      (node (ref "R75") (pin "2") (pinfunction "E_2") (pintype "passive"))
      (node (ref "R99") (pin "2") (pinfunction "E_2") (pintype "passive"))
      (node (ref "ZOLD_3P12") (pin "2") (pinfunction "1_2") (pintype "passive"))
    )
    (net (code "144") (name "Net-(R51-E)") (class "Default")
      (node (ref "R51") (pin "2") (pinfunction "E_2") (pintype "passive"))
      (node (ref "U16") (pin "P$6") (pinfunction "D_P$6") (pintype "passive"))
    )
    (net (code "145") (name "Net-(R52-E)") (class "Default")
      (node (ref "R52") (pin "2") (pinfunction "E_2") (pintype "passive"))
      (node (ref "U16") (pin "P$4") (pinfunction "D_P$4") (pintype "passive"))
    )
    (net (code "146") (name "Net-(R100-E)") (class "Default")
      (node (ref "R100") (pin "2") (pinfunction "E_2") (pintype "passive"))
      (node (ref "R52") (pin "1") (pinfunction "A_1") (pintype "passive"))
      (node (ref "R76") (pin "2") (pinfunction "E_2") (pintype "passive"))
      (node (ref "ZOLD_3P12") (pin "3") (pinfunction "1_3") (pintype "passive"))
    )
    (net (code "147") (name "Net-(R125-E)") (class "Default")
      (node (ref "CN_CANLEZAR") (pin "1") (pinfunction "1_1") (pintype "passive"))
      (node (ref "R125") (pin "2") (pinfunction "E_2") (pintype "passive"))
    )
    (net (code "148") (name "Net-(R126-A)") (class "Default")
      (node (ref "CN_CANLEZAR") (pin "3") (pinfunction "3_3") (pintype "passive"))
      (node (ref "R126") (pin "1") (pinfunction "A_1") (pintype "passive"))
    )
    (net (code "149") (name "unconnected-(CANIC-VREF-Pad5)") (class "Default")
      (node (ref "CANIC") (pin "5") (pinfunction "VREF_5") (pintype "output"))
    )
    (net (code "150") (name "unconnected-(CN_RJ1-Pad1)") (class "Default")
      (node (ref "CN_RJ1") (pin "1") (pinfunction "1_1") (pintype "passive"))
    )
    (net (code "151") (name "unconnected-(CN_RJ1-Pad2)") (class "Default")
      (node (ref "CN_RJ1") (pin "2") (pinfunction "2_2") (pintype "passive"))
    )
    (net (code "152") (name "unconnected-(CN_RJ1-Pad3)") (class "Default")
      (node (ref "CN_RJ1") (pin "3") (pinfunction "3_3") (pintype "passive"))
    )
    (net (code "153") (name "unconnected-(CN_RJ1-Pad6)") (class "Default")
      (node (ref "CN_RJ1") (pin "6") (pinfunction "6_6") (pintype "passive"))
    )
    (net (code "154") (name "unconnected-(CN_RJ2-Pad1)") (class "Default")
      (node (ref "CN_RJ2") (pin "1") (pinfunction "1_1") (pintype "passive"))
    )
    (net (code "155") (name "unconnected-(CN_RJ2-Pad2)") (class "Default")
      (node (ref "CN_RJ2") (pin "2") (pinfunction "2_2") (pintype "passive"))
    )
    (net (code "156") (name "unconnected-(CN_RJ2-Pad3)") (class "Default")
      (node (ref "CN_RJ2") (pin "3") (pinfunction "3_3") (pintype "passive"))
    )
    (net (code "157") (name "unconnected-(CN_RJ2-Pad6)") (class "Default")
      (node (ref "CN_RJ2") (pin "6") (pinfunction "6_6") (pintype "passive"))
    )
    (net (code "158") (name "unconnected-(IC9-14_SDO-Pad14)") (class "Default")
      (node (ref "IC9") (pin "14") (pinfunction "14_SDO_14") (pintype "output"))
    )
    (net (code "159") (name "unconnected-(PIC1-NC-Pad34)") (class "Default")
      (node (ref "PIC1") (pin "34") (pinfunction "NC_34") (pintype "no_connect"))
    )
    (net (code "160") (name "unconnected-(PIC1-NC_2-Pad12)") (class "Default")
      (node (ref "PIC1") (pin "12") (pinfunction "NC_2_12") (pintype "no_connect"))
    )
    (net (code "161") (name "unconnected-(PIC1-NC_3-Pad13)") (class "Default")
      (node (ref "PIC1") (pin "13") (pinfunction "NC_3_13") (pintype "no_connect"))
    )
    (net (code "162") (name "unconnected-(PIC1-NC_4-Pad33)") (class "Default")
      (node (ref "PIC1") (pin "33") (pinfunction "NC_4_33") (pintype "no_connect"))
    )
    (net (code "163") (name "unconnected-(PIC1-RE0{slash}~{RD{slash}AN5}-Pad25)") (class "Default")
      (node (ref "PIC1") (pin "25") (pinfunction "RE0/~{RD/AN5}_25") (pintype "bidirectional"))
    )
    (net (code "164") (name "unconnected-(U$20-PadP$2)") (class "Default")
      (node (ref "U$20") (pin "P$2") (pinfunction "P$2_P$2") (pintype "bidirectional"))
    )
  )
)
